# mainBoard_GTernal_1-0_v12.net
KiCad netlist of a schematic drawn in EAGLE
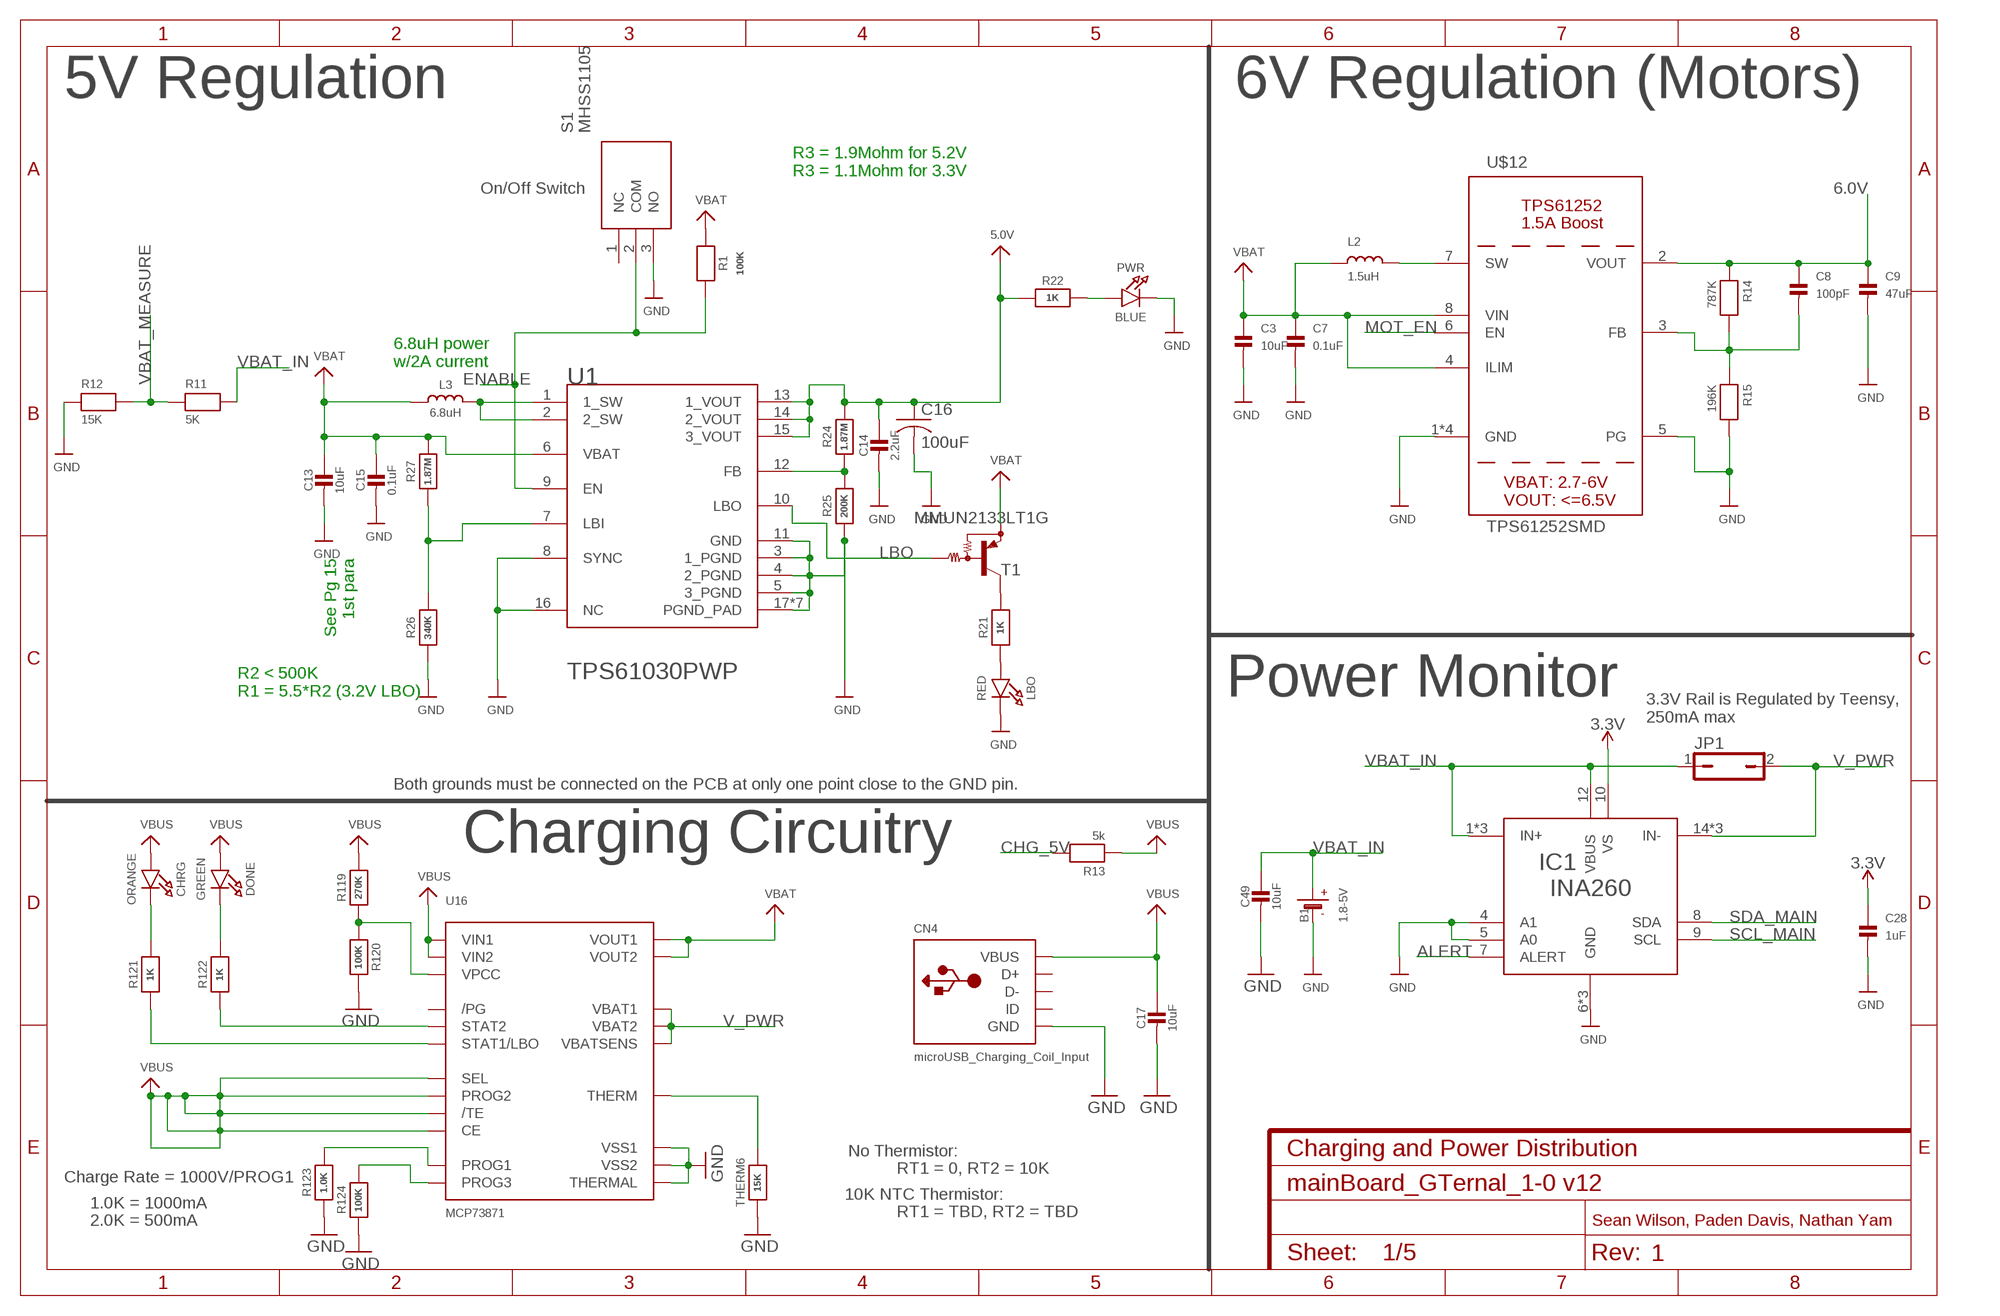
[diagram p0: schematic, sheet 1]
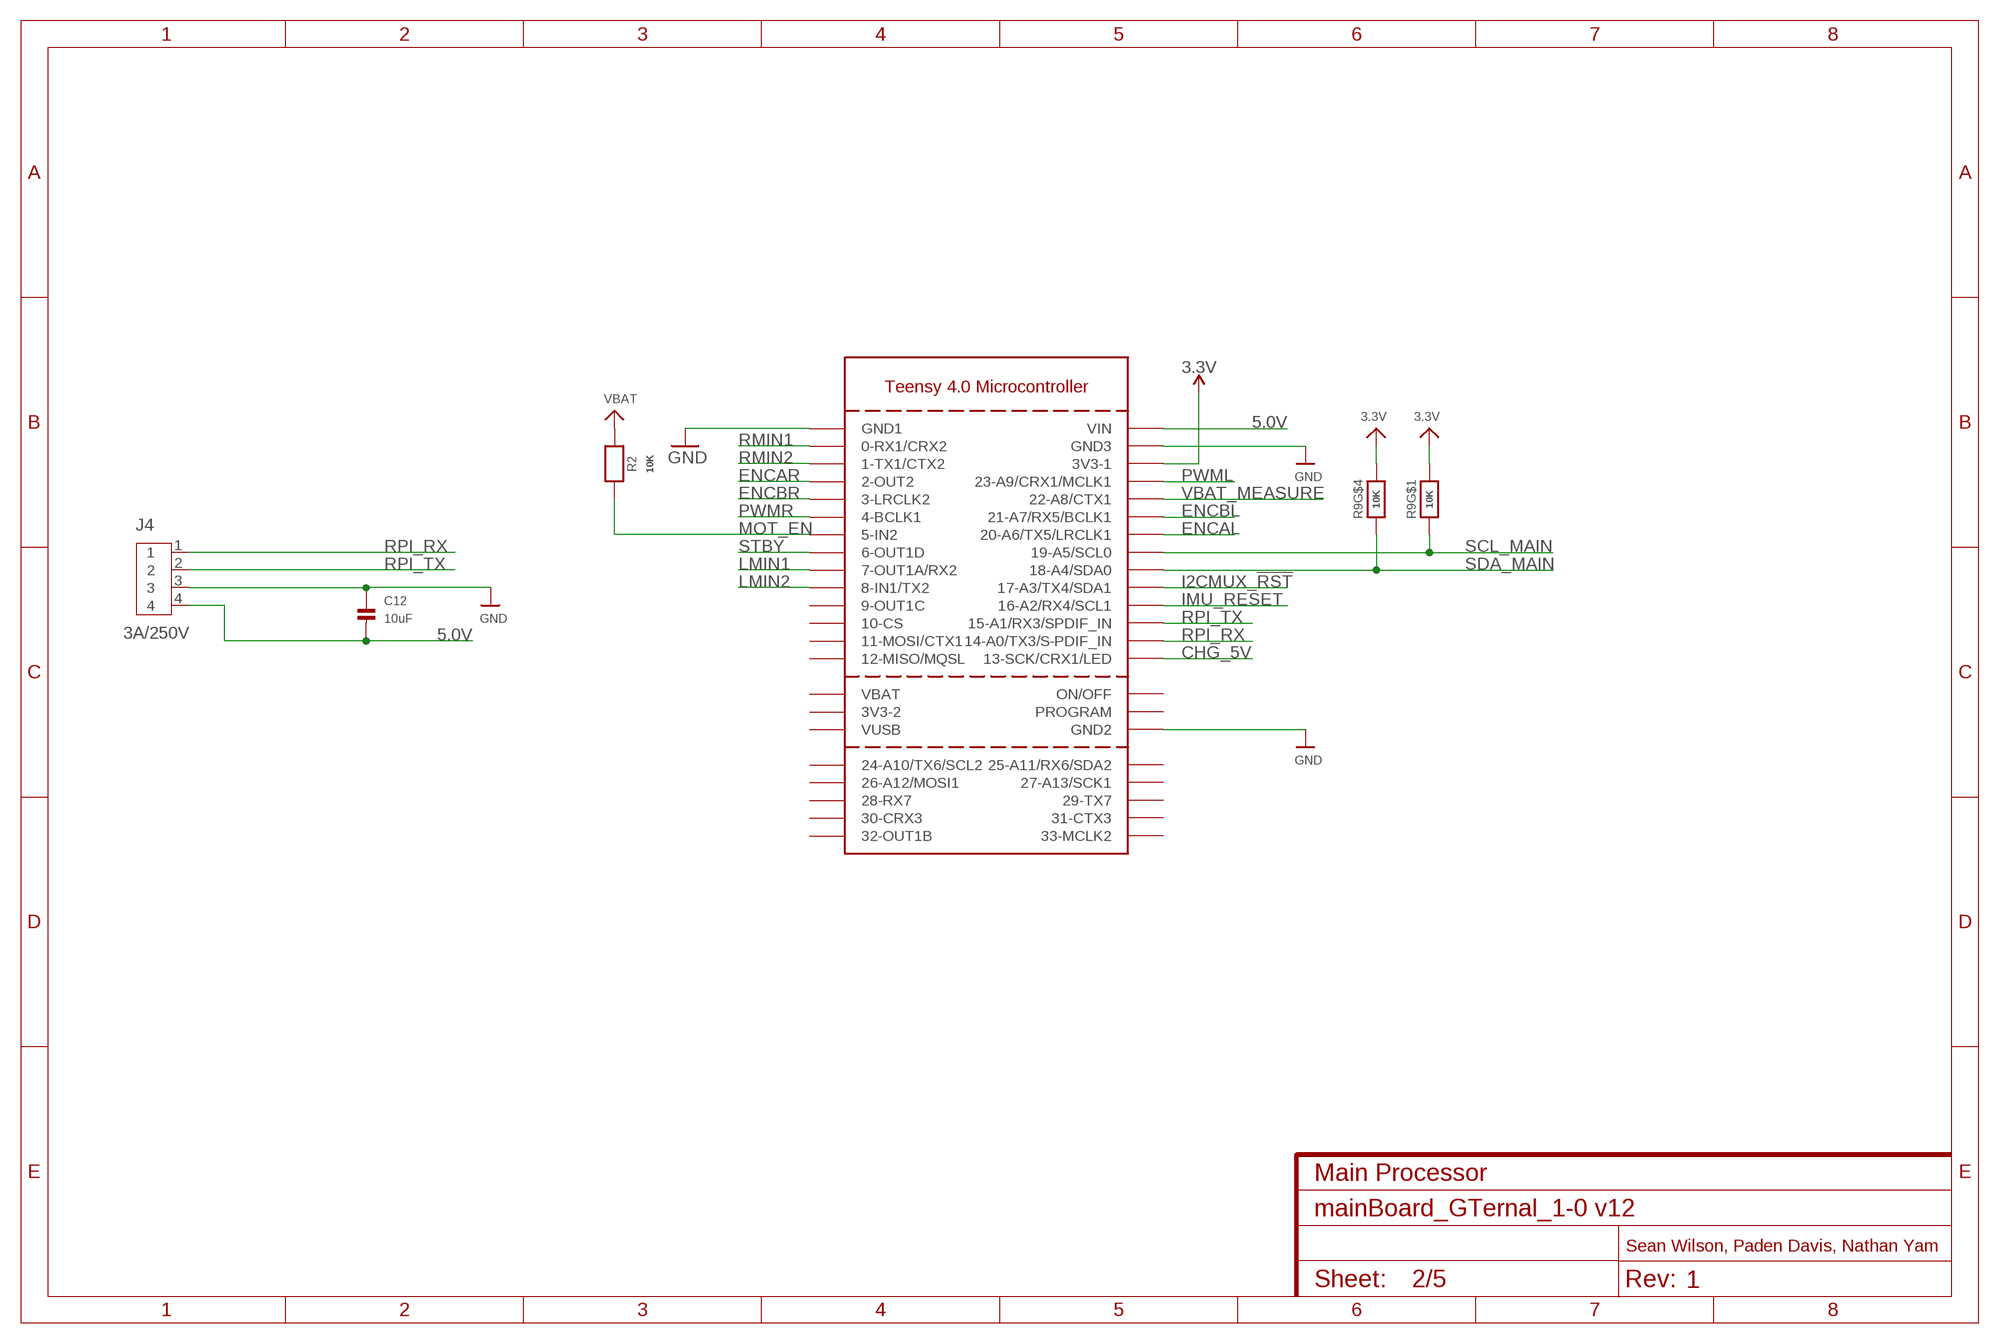
[diagram p1: schematic, sheet 2]
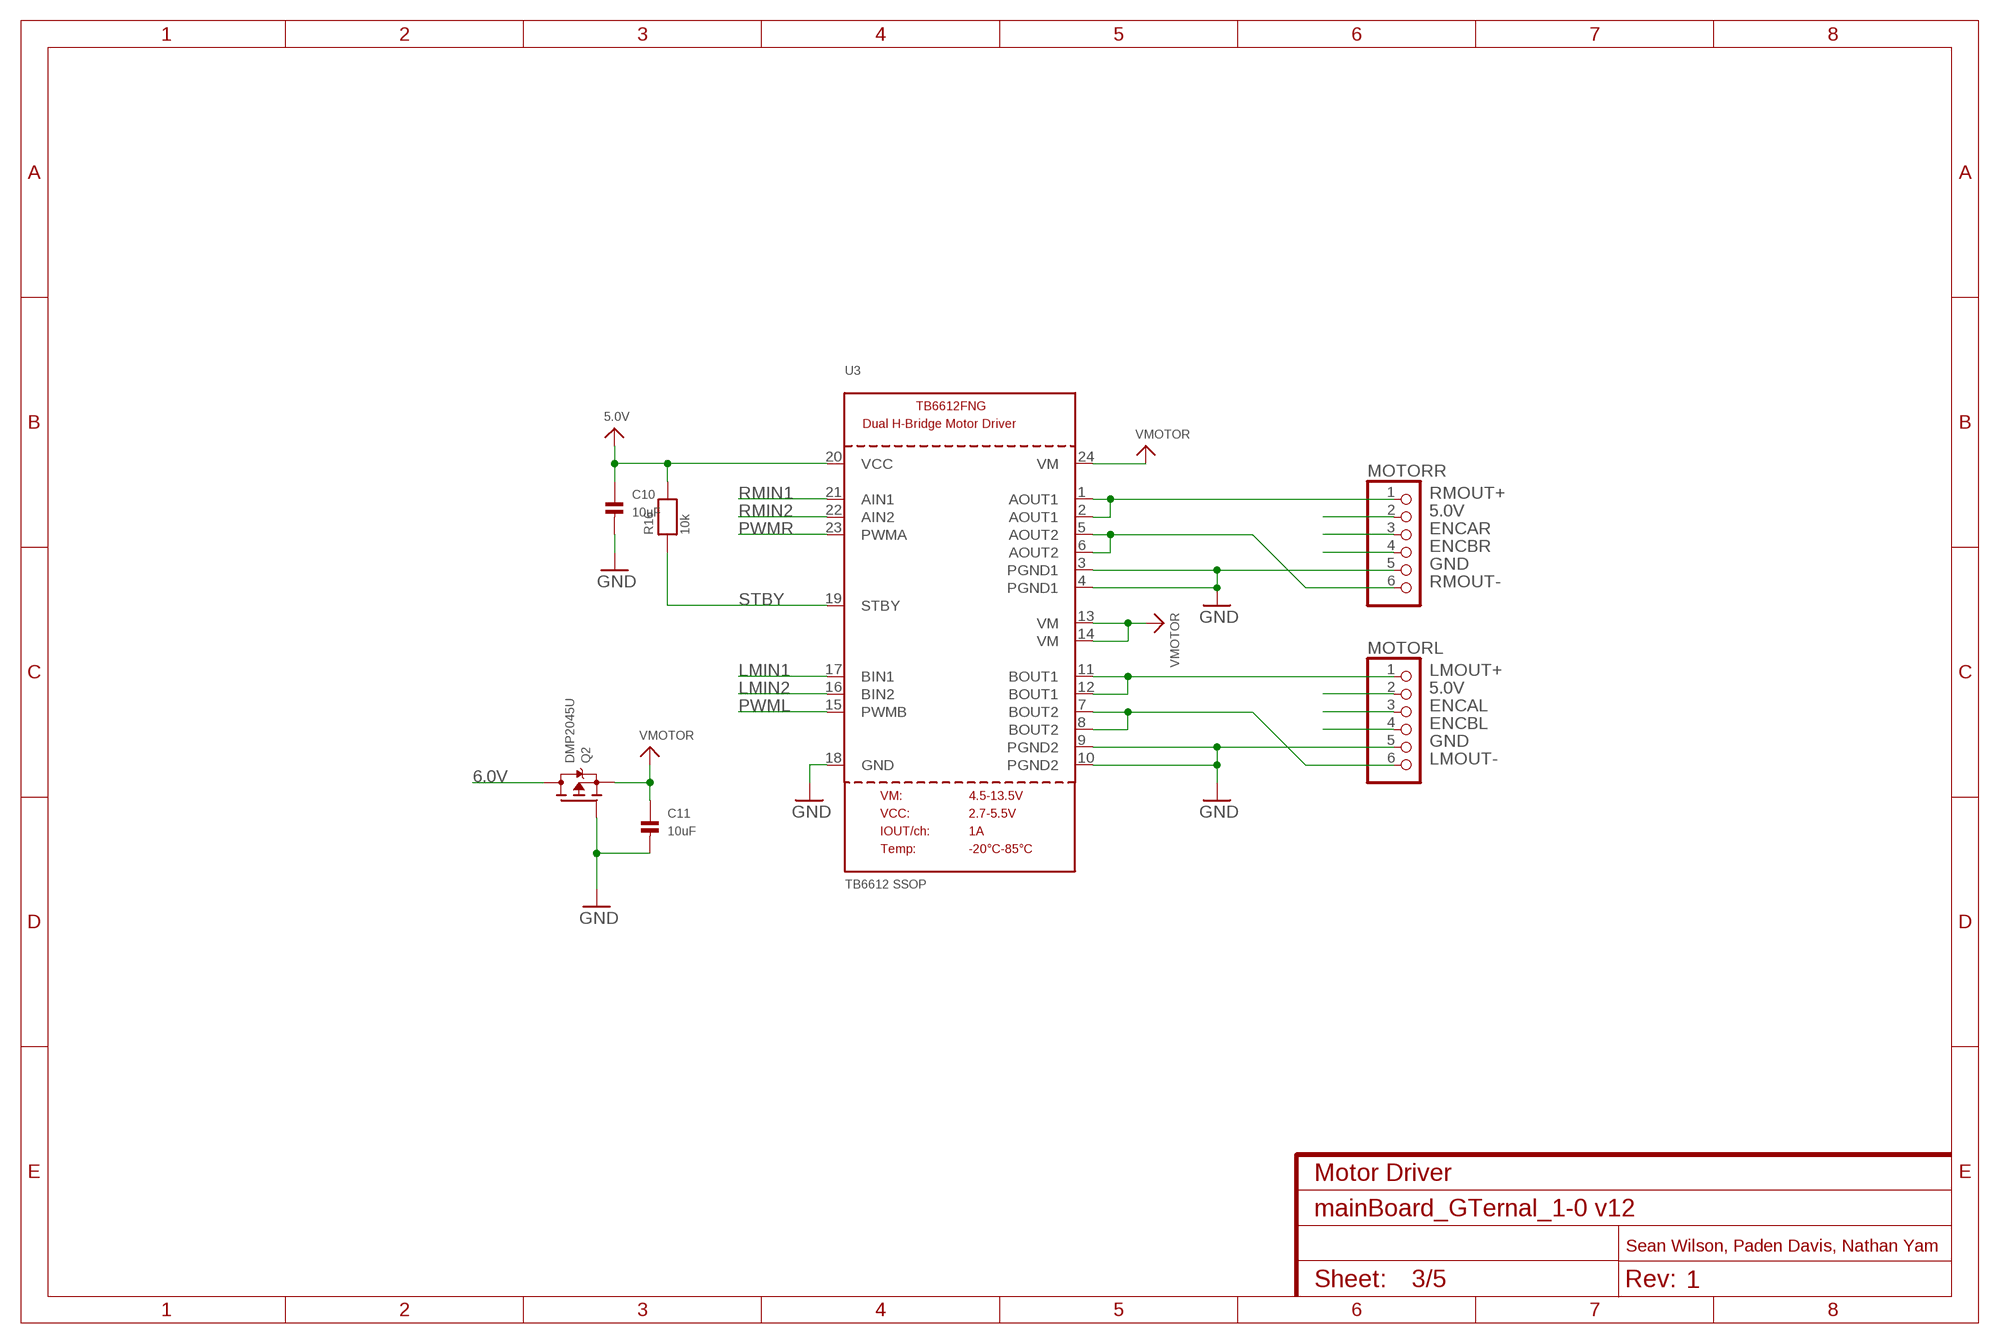
[diagram p2: schematic, sheet 3]
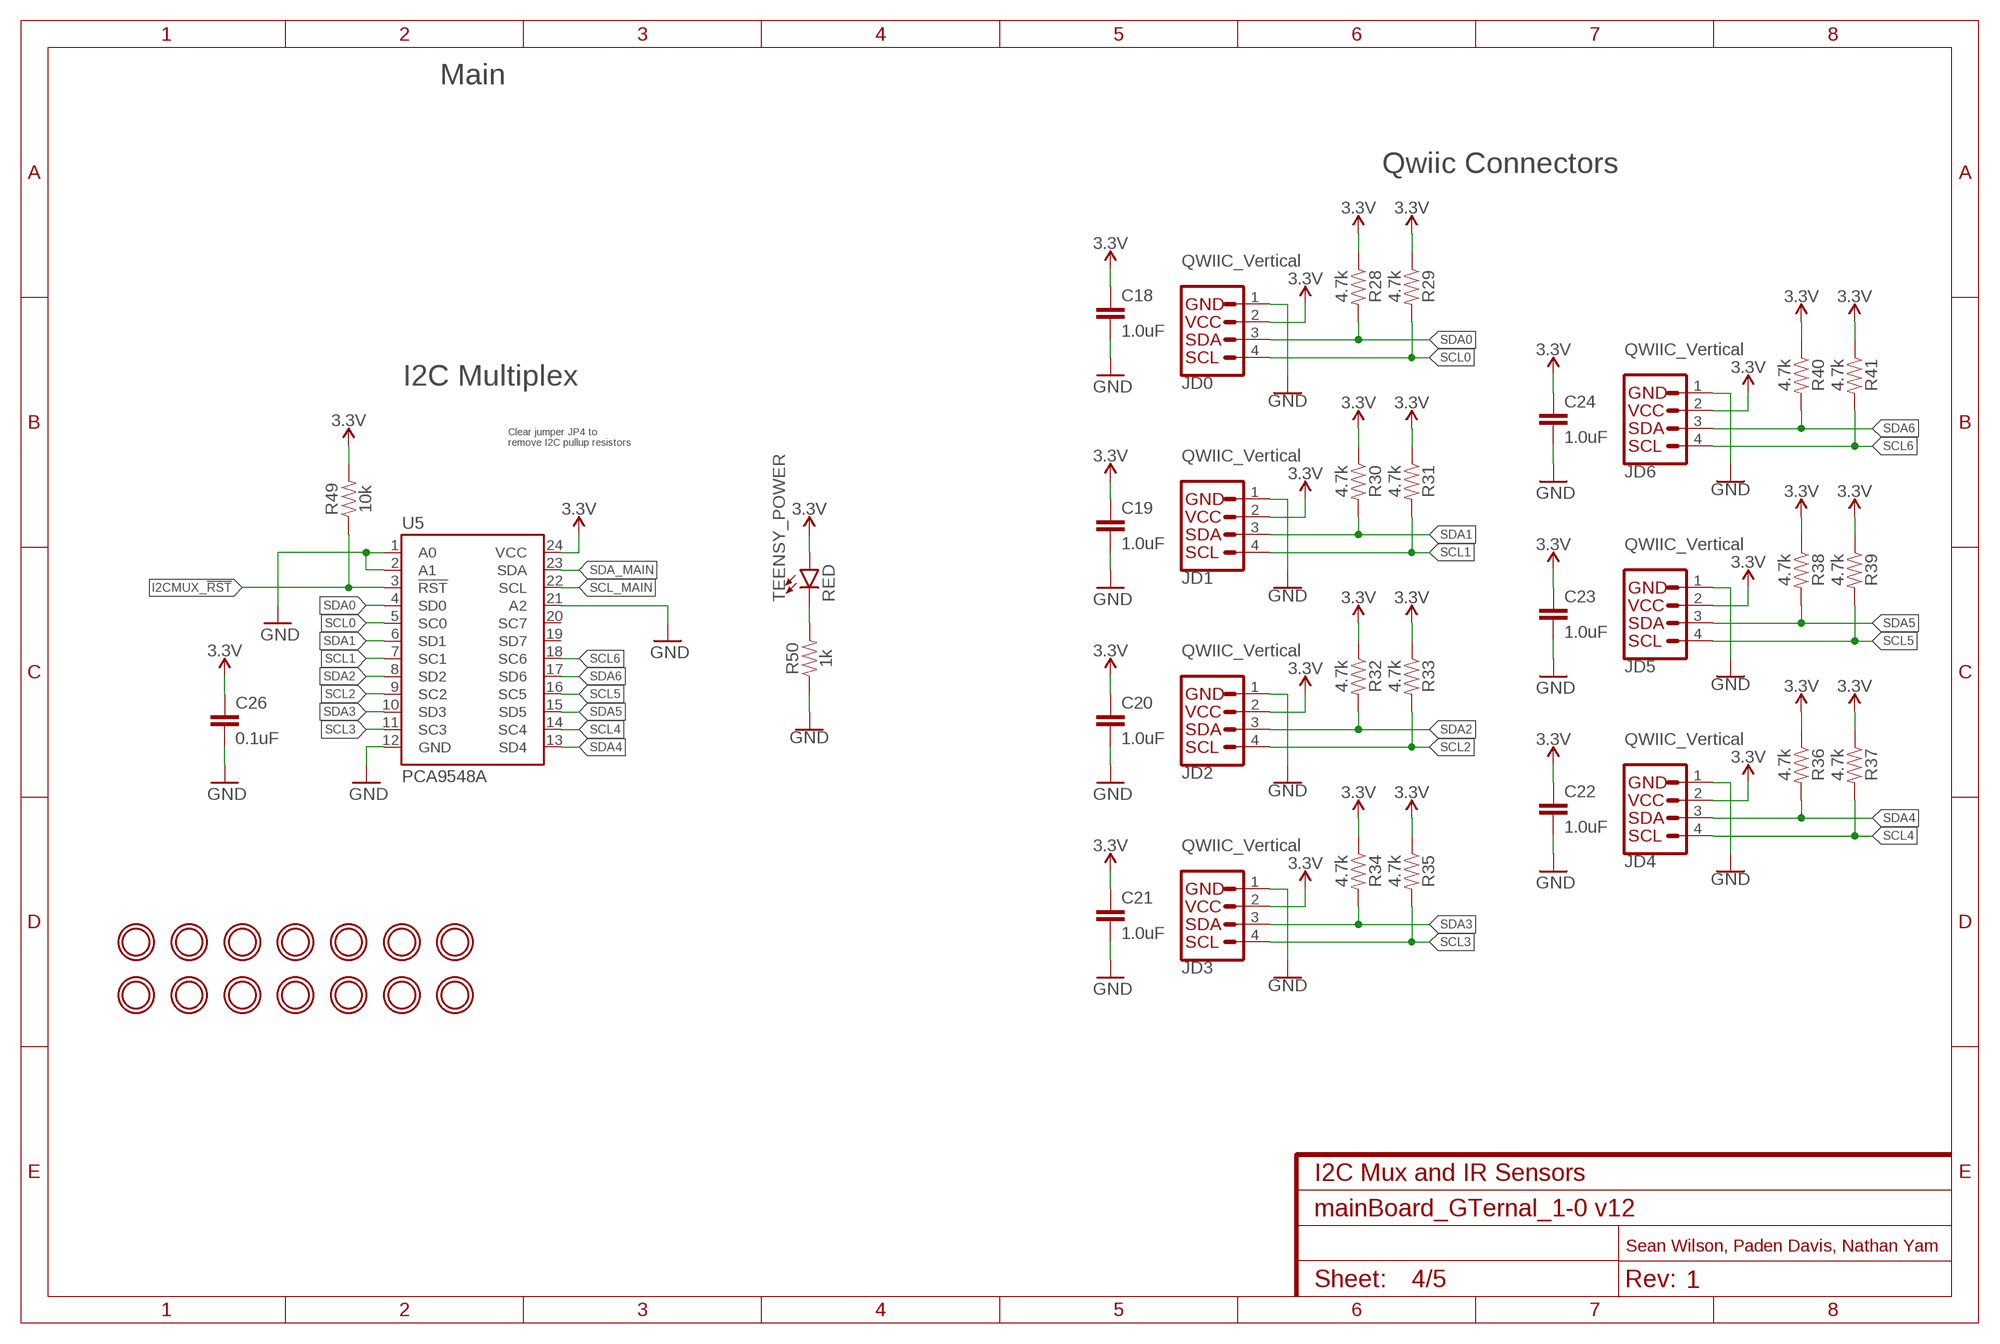
[diagram p3: schematic, sheet 4]
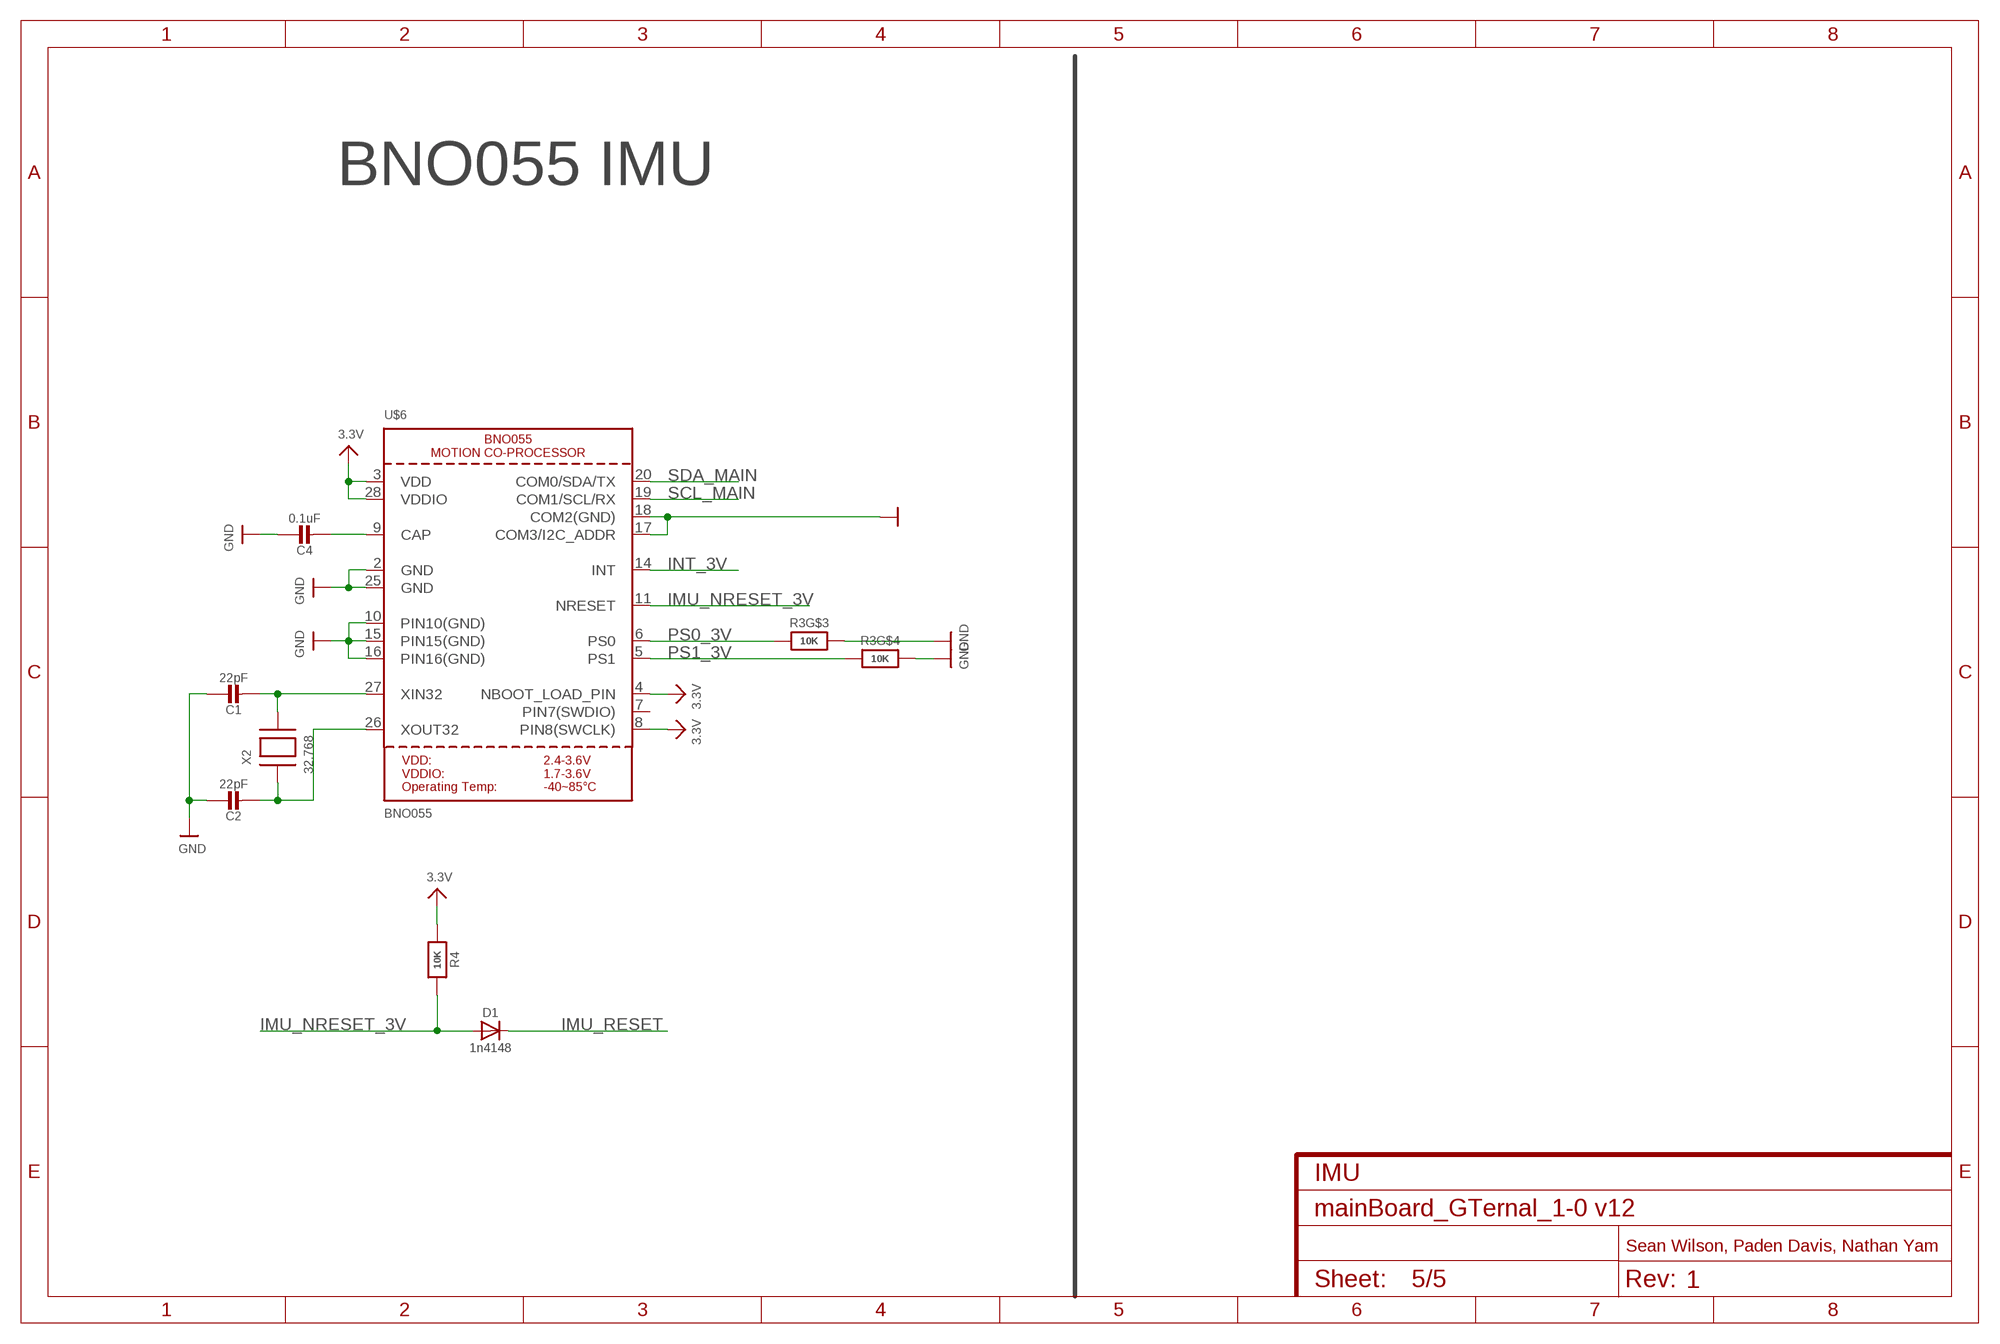
[diagram p4: schematic, sheet 5]

(export (version "E")
  (design (tool "Eeschema 10.0.6"))
  (components
    (comp (ref "C18")
      (value "1.0uF")
      (footprint "eagle-import:0603")
      (libsource (lib "eagle-import") (part "1.0UF-0603-16V-10%"))
    )
    (comp (ref "C19")
      (value "1.0uF")
      (footprint "eagle-import:0603")
      (libsource (lib "eagle-import") (part "1.0UF-0603-16V-10%"))
    )
    (comp (ref "C20")
      (value "1.0uF")
      (footprint "eagle-import:0603")
      (libsource (lib "eagle-import") (part "1.0UF-0603-16V-10%"))
    )
    (comp (ref "C21")
      (value "1.0uF")
      (footprint "eagle-import:0603")
      (libsource (lib "eagle-import") (part "1.0UF-0603-16V-10%"))
    )
    (comp (ref "C22")
      (value "1.0uF")
      (footprint "eagle-import:0603")
      (libsource (lib "eagle-import") (part "1.0UF-0603-16V-10%"))
    )
    (comp (ref "C23")
      (value "1.0uF")
      (footprint "eagle-import:0603")
      (libsource (lib "eagle-import") (part "1.0UF-0603-16V-10%"))
    )
    (comp (ref "C24")
      (value "1.0uF")
      (footprint "eagle-import:0603")
      (libsource (lib "eagle-import") (part "1.0UF-0603-16V-10%"))
    )
    (comp (ref "C26")
      (value "0.1uF")
      (footprint "eagle-import:0603")
      (libsource (lib "eagle-import") (part "0.1UF-0603-25V-(+80/-20%)"))
    )
    (comp (ref "JD0")
      (value "QWIIC_Vertical")
      (footprint "eagle-import:JST04_1MM_VERT")
      (libsource (lib "eagle-import") (part "QWIIC_CONNECTOR"))
    )
    (comp (ref "JD1")
      (value "QWIIC_Vertical")
      (footprint "eagle-import:JST04_1MM_VERT")
      (libsource (lib "eagle-import") (part "QWIIC_CONNECTOR"))
    )
    (comp (ref "JD2")
      (value "QWIIC_Vertical")
      (footprint "eagle-import:JST04_1MM_VERT")
      (libsource (lib "eagle-import") (part "QWIIC_CONNECTOR"))
    )
    (comp (ref "JD3")
      (value "QWIIC_Vertical")
      (footprint "eagle-import:JST04_1MM_VERT")
      (libsource (lib "eagle-import") (part "QWIIC_CONNECTOR"))
    )
    (comp (ref "JD4")
      (value "QWIIC_Vertical")
      (footprint "eagle-import:JST04_1MM_VERT")
      (libsource (lib "eagle-import") (part "QWIIC_CONNECTOR"))
    )
    (comp (ref "JD5")
      (value "QWIIC_Vertical")
      (footprint "eagle-import:JST04_1MM_VERT")
      (libsource (lib "eagle-import") (part "QWIIC_CONNECTOR"))
    )
    (comp (ref "JD6")
      (value "QWIIC_Vertical")
      (footprint "eagle-import:JST04_1MM_VERT")
      (libsource (lib "eagle-import") (part "QWIIC_CONNECTOR"))
    )
    (comp (ref "R28")
      (value "4.7k")
      (footprint "eagle-import:0603")
      (libsource (lib "eagle-import") (part "4.7KOHM-0603-1/10W-1%"))
    )
    (comp (ref "R29")
      (value "4.7k")
      (footprint "eagle-import:0603")
      (libsource (lib "eagle-import") (part "4.7KOHM-0603-1/10W-1%"))
    )
    (comp (ref "R30")
      (value "4.7k")
      (footprint "eagle-import:0603")
      (libsource (lib "eagle-import") (part "4.7KOHM-0603-1/10W-1%"))
    )
    (comp (ref "R31")
      (value "4.7k")
      (footprint "eagle-import:0603")
      (libsource (lib "eagle-import") (part "4.7KOHM-0603-1/10W-1%"))
    )
    (comp (ref "R32")
      (value "4.7k")
      (footprint "eagle-import:0603")
      (libsource (lib "eagle-import") (part "4.7KOHM-0603-1/10W-1%"))
    )
    (comp (ref "R33")
      (value "4.7k")
      (footprint "eagle-import:0603")
      (libsource (lib "eagle-import") (part "4.7KOHM-0603-1/10W-1%"))
    )
    (comp (ref "R34")
      (value "4.7k")
      (footprint "eagle-import:0603")
      (libsource (lib "eagle-import") (part "4.7KOHM-0603-1/10W-1%"))
    )
    (comp (ref "R35")
      (value "4.7k")
      (footprint "eagle-import:0603")
      (libsource (lib "eagle-import") (part "4.7KOHM-0603-1/10W-1%"))
    )
    (comp (ref "R36")
      (value "4.7k")
      (footprint "eagle-import:0603")
      (libsource (lib "eagle-import") (part "4.7KOHM-0603-1/10W-1%"))
    )
    (comp (ref "R37")
      (value "4.7k")
      (footprint "eagle-import:0603")
      (libsource (lib "eagle-import") (part "4.7KOHM-0603-1/10W-1%"))
    )
    (comp (ref "R38")
      (value "4.7k")
      (footprint "eagle-import:0603")
      (libsource (lib "eagle-import") (part "4.7KOHM-0603-1/10W-1%"))
    )
    (comp (ref "R39")
      (value "4.7k")
      (footprint "eagle-import:0603")
      (libsource (lib "eagle-import") (part "4.7KOHM-0603-1/10W-1%"))
    )
    (comp (ref "R40")
      (value "4.7k")
      (footprint "eagle-import:0603")
      (libsource (lib "eagle-import") (part "4.7KOHM-0603-1/10W-1%"))
    )
    (comp (ref "R41")
      (value "4.7k")
      (footprint "eagle-import:0603")
      (libsource (lib "eagle-import") (part "4.7KOHM-0603-1/10W-1%"))
    )
    (comp (ref "R49")
      (value "10k")
      (footprint "eagle-import:0603")
      (libsource (lib "eagle-import") (part "10KOHM-0603-1/10W-1%"))
    )
    (comp (ref "R50")
      (value "1k")
      (footprint "eagle-import:0603")
      (libsource (lib "eagle-import") (part "1KOHM-0603-1/10W-1%"))
    )
    (comp (ref "TEENSY_POWER")
      (value "RED")
      (footprint "eagle-import:LED-0603")
      (libsource (lib "eagle-import") (part "LED-RED0603"))
    )
    (comp (ref "U$8")
      (value "MOUNTINGHOLE2.5")
      (footprint "eagle-import:MOUNTINGHOLE_2.5_PLATED")
      (libsource (lib "eagle-import") (part "MOUNTINGHOLE2.5"))
    )
    (comp (ref "U$30")
      (value "MOUNTINGHOLE2.5")
      (footprint "eagle-import:MOUNTINGHOLE_2.5_PLATED")
      (libsource (lib "eagle-import") (part "MOUNTINGHOLE2.5"))
    )
    (comp (ref "U$31")
      (value "MOUNTINGHOLE2.5")
      (footprint "eagle-import:MOUNTINGHOLE_2.5_PLATED")
      (libsource (lib "eagle-import") (part "MOUNTINGHOLE2.5"))
    )
    (comp (ref "U$32")
      (value "MOUNTINGHOLE2.5")
      (footprint "eagle-import:MOUNTINGHOLE_2.5_PLATED")
      (libsource (lib "eagle-import") (part "MOUNTINGHOLE2.5"))
    )
    (comp (ref "U$33")
      (value "MOUNTINGHOLE2.5")
      (footprint "eagle-import:MOUNTINGHOLE_2.5_PLATED")
      (libsource (lib "eagle-import") (part "MOUNTINGHOLE2.5"))
    )
    (comp (ref "U$34")
      (value "MOUNTINGHOLE2.5")
      (footprint "eagle-import:MOUNTINGHOLE_2.5_PLATED")
      (libsource (lib "eagle-import") (part "MOUNTINGHOLE2.5"))
    )
    (comp (ref "U$35")
      (value "MOUNTINGHOLE2.5")
      (footprint "eagle-import:MOUNTINGHOLE_2.5_PLATED")
      (libsource (lib "eagle-import") (part "MOUNTINGHOLE2.5"))
    )
    (comp (ref "U$36")
      (value "MOUNTINGHOLE2.5")
      (footprint "eagle-import:MOUNTINGHOLE_2.5_PLATED")
      (libsource (lib "eagle-import") (part "MOUNTINGHOLE2.5"))
    )
    (comp (ref "U$37")
      (value "MOUNTINGHOLE2.5")
      (footprint "eagle-import:MOUNTINGHOLE_2.5_PLATED")
      (libsource (lib "eagle-import") (part "MOUNTINGHOLE2.5"))
    )
    (comp (ref "U$43")
      (value "MOUNTINGHOLE2.5")
      (footprint "eagle-import:MOUNTINGHOLE_2.5_PLATED")
      (libsource (lib "eagle-import") (part "MOUNTINGHOLE2.5"))
    )
    (comp (ref "U$45")
      (value "MOUNTINGHOLE2.5")
      (footprint "eagle-import:MOUNTINGHOLE_2.5_PLATED")
      (libsource (lib "eagle-import") (part "MOUNTINGHOLE2.5"))
    )
    (comp (ref "U$46")
      (value "MOUNTINGHOLE2.5")
      (footprint "eagle-import:MOUNTINGHOLE_2.5_PLATED")
      (libsource (lib "eagle-import") (part "MOUNTINGHOLE2.5"))
    )
    (comp (ref "U$47")
      (value "MOUNTINGHOLE2.5")
      (footprint "eagle-import:MOUNTINGHOLE_2.5_PLATED")
      (libsource (lib "eagle-import") (part "MOUNTINGHOLE2.5"))
    )
    (comp (ref "U$48")
      (value "MOUNTINGHOLE2.5")
      (footprint "eagle-import:MOUNTINGHOLE_2.5_PLATED")
      (libsource (lib "eagle-import") (part "MOUNTINGHOLE2.5"))
    )
    (comp (ref "U5")
      (value "PCA9548A")
      (footprint "eagle-import:TSSOP28")
      (libsource (lib "eagle-import") (part "PCA9548A"))
    )
    (comp (ref "C1")
      (value "22pF")
      (footprint "eagle-import:0603-NO")
      (libsource (lib "eagle-import") (part "CAP_CERAMIC0603_NO"))
    )
    (comp (ref "C2")
      (value "22pF")
      (footprint "eagle-import:0603-NO")
      (libsource (lib "eagle-import") (part "CAP_CERAMIC0603_NO"))
    )
    (comp (ref "C4")
      (value "0.1uF")
      (footprint "eagle-import:0603-NO")
      (libsource (lib "eagle-import") (part "CAP_CERAMIC0603_NO"))
    )
    (comp (ref "D1")
      (value "1n4148")
      (footprint "eagle-import:SOD-323")
      (libsource (lib "eagle-import") (part "DIODESOD-323"))
    )
    (comp (ref "R3")
      (value "10K")
      (footprint "eagle-import:RESPACK_4X0603")
      (libsource (lib "eagle-import") (part "RESISTOR_4PACK"))
    )
    (comp (ref "R4")
      (value "10K")
      (footprint "eagle-import:0603-NO")
      (libsource (lib "eagle-import") (part "RESISTOR_0603_NOOUT"))
    )
    (comp (ref "U$6")
      (value "BNO055")
      (footprint "eagle-import:BNO055")
      (libsource (lib "eagle-import") (part "BNO055"))
    )
    (comp (ref "X2")
      (value "32.768")
      (footprint "eagle-import:XTAL3215")
      (libsource (lib "eagle-import") (part "XTAL-3.2X1.5"))
    )
    (comp (ref "C10")
      (value "10uF")
      (footprint "eagle-import:0603")
      (libsource (lib "eagle-import") (part "CAP_CERAMIC0603"))
    )
    (comp (ref "C11")
      (value "10uF")
      (footprint "eagle-import:0603")
      (libsource (lib "eagle-import") (part "CAP_CERAMIC0603"))
    )
    (comp (ref "MOTORL")
      (value "PINHD-1X6CB")
      (footprint "eagle-import:1X06-CLEANBIG")
      (libsource (lib "eagle-import") (part "PINHD-1X6CB"))
    )
    (comp (ref "MOTORR")
      (value "PINHD-1X6CB")
      (footprint "eagle-import:1X06-CLEANBIG")
      (libsource (lib "eagle-import") (part "PINHD-1X6CB"))
    )
    (comp (ref "Q2")
      (value "DMP2045U")
      (footprint "eagle-import:SOT23-WIDE")
      (libsource (lib "eagle-import") (part "MOSFET-PWIDE"))
    )
    (comp (ref "R16")
      (value "10k")
      (footprint "eagle-import:0805")
      (libsource (lib "eagle-import") (part "RESISTOR0805"))
    )
    (comp (ref "U3")
      (value "TB6612 SSOP")
      (footprint "eagle-import:SSOP24")
      (libsource (lib "eagle-import") (part "TB6612FNGSSOP"))
    )
    (comp (ref "C12")
      (value "10uF")
      (footprint "eagle-import:0603")
      (libsource (lib "eagle-import") (part "CAP_CERAMIC0603"))
    )
    (comp (ref "J4")
      (value "3A/250V")
      (footprint "eagle-import:B4B-XH-A")
      (fields (field (name "MANUFACTURER") "JST (XH connector)") (field (name "MPN") "B4B-XH-A"))
      (libsource (lib "eagle-import") (part "B4B-XH-A"))
    )
    (comp (ref "R2")
      (value "10K")
      (footprint "eagle-import:0805-NO")
      (libsource (lib "eagle-import") (part "RESISTOR0805_NOOUTLINE"))
    )
    (comp (ref "R9")
      (value "10K")
      (footprint "eagle-import:RESPACK_4X0603")
      (libsource (lib "eagle-import") (part "RESISTOR_4PACK"))
    )
    (comp (ref "U$57")
      (value "TEENSY40")
      (footprint "eagle-import:TEENSY40")
      (libsource (lib "eagle-import") (part "TEENSY40"))
    )
    (comp (ref "B1")
      (value "1.8-5V")
      (footprint "eagle-import:JSTPH2")
      (libsource (lib "eagle-import") (part "BATTERY"))
    )
    (comp (ref "C3")
      (value "10uF")
      (footprint "eagle-import:0603")
      (libsource (lib "eagle-import") (part "CAP_CERAMIC0603"))
    )
    (comp (ref "C7")
      (value "0.1uF")
      (footprint "eagle-import:0805")
      (libsource (lib "eagle-import") (part "CAP_CERAMIC0805"))
    )
    (comp (ref "C8")
      (value "100pF")
      (footprint "eagle-import:0603")
      (libsource (lib "eagle-import") (part "CAP_CERAMIC0603"))
    )
    (comp (ref "C9")
      (value "47uF")
      (footprint "eagle-import:1206")
      (libsource (lib "eagle-import") (part "CAP_CERAMIC1206"))
    )
    (comp (ref "C13")
      (value "10uF")
      (footprint "eagle-import:0805-NO")
      (libsource (lib "eagle-import") (part "CAP_CERAMIC0805-NOOUTLINE"))
    )
    (comp (ref "C14")
      (value "2.2uF")
      (footprint "eagle-import:0805-NO")
      (libsource (lib "eagle-import") (part "CAP_CERAMIC0805-NOOUTLINE"))
    )
    (comp (ref "C15")
      (value "0.1uF")
      (footprint "eagle-import:0805_10MGAP")
      (libsource (lib "eagle-import") (part "CAP_CERAMIC0805_10MGAP"))
    )
    (comp (ref "C16")
      (value "100uF")
      (footprint "eagle-import:C1210")
      (libsource (lib "eagle-import") (part "C-USC1210"))
    )
    (comp (ref "C17")
      (value "10uF")
      (footprint "eagle-import:0805-NO")
      (libsource (lib "eagle-import") (part "CAP_CERAMIC0805-NOOUTLINE"))
    )
    (comp (ref "C28")
      (value "1uF")
      (footprint "eagle-import:0603-NO")
      (libsource (lib "eagle-import") (part "CAP_CERAMIC0603_NO"))
    )
    (comp (ref "C49")
      (value "10uF")
      (footprint "eagle-import:0805-NO")
      (libsource (lib "eagle-import") (part "CAP_CERAMIC0805-NOOUTLINE"))
    )
    (comp (ref "CHRG")
      (value "ORANGE")
      (footprint "eagle-import:CHIPLED_0805_NOOUTLINE")
      (libsource (lib "eagle-import") (part "LED0805_NOOUTLINE"))
    )
    (comp (ref "CN4")
      (value "microUSB_Charging_Coil_Input")
      (footprint "eagle-import:4UCONN_20329")
      (libsource (lib "eagle-import") (part "USBMICRO_20329"))
    )
    (comp (ref "DONE")
      (value "GREEN")
      (footprint "eagle-import:CHIPLED_0805_NOOUTLINE")
      (libsource (lib "eagle-import") (part "LED0805_NOOUTLINE"))
    )
    (comp (ref "IC1")
      (value "INA260")
      (footprint "eagle-import:TSSOP16")
      (libsource (lib "eagle-import") (part "INA260"))
    )
    (comp (ref "JP1")
      (value "JP1Q")
      (footprint "eagle-import:JP1")
      (libsource (lib "eagle-import") (part "JP1Q"))
    )
    (comp (ref "L2")
      (value "1.5uH")
      (footprint "eagle-import:MURATA_DFE252012P-1R5M=P2")
      (libsource (lib "eagle-import") (part "MURATA_DFE252012P-1R5M=P2"))
    )
    (comp (ref "L3")
      (value "6.8uH")
      (footprint "eagle-import:INDUCTOR_5X5MM_TDK_VLC5045")
      (libsource (lib "eagle-import") (part "INDUCTORTDK_VLC5045"))
    )
    (comp (ref "LBO")
      (value "RED")
      (footprint "eagle-import:CHIPLED_0805_NOOUTLINE")
      (libsource (lib "eagle-import") (part "LED0805_NOOUTLINE"))
    )
    (comp (ref "PWR")
      (value "BLUE")
      (footprint "eagle-import:CHIPLED_0805_NOOUTLINE")
      (libsource (lib "eagle-import") (part "LED0805_NOOUTLINE"))
    )
    (comp (ref "R1")
      (value "100K")
      (footprint "eagle-import:0805-NO")
      (libsource (lib "eagle-import") (part "RESISTOR0805_NOOUTLINE"))
    )
    (comp (ref "R11")
      (value "5K")
      (footprint "eagle-import:0805")
      (libsource (lib "eagle-import") (part "RESISTOR0805"))
    )
    (comp (ref "R12")
      (value "15K")
      (footprint "eagle-import:0805")
      (libsource (lib "eagle-import") (part "RESISTOR0805"))
    )
    (comp (ref "R13")
      (value "5k")
      (footprint "eagle-import:0805")
      (libsource (lib "eagle-import") (part "RESISTOR0805"))
    )
    (comp (ref "R14")
      (value "787K")
      (footprint "eagle-import:0805")
      (libsource (lib "eagle-import") (part "RESISTOR0805"))
    )
    (comp (ref "R15")
      (value "196K")
      (footprint "eagle-import:0805")
      (libsource (lib "eagle-import") (part "RESISTOR0805"))
    )
    (comp (ref "R21")
      (value "1K")
      (footprint "eagle-import:0805-NO")
      (libsource (lib "eagle-import") (part "RESISTOR0805_NOOUTLINE"))
    )
    (comp (ref "R22")
      (value "1K")
      (footprint "eagle-import:0805-NO")
      (libsource (lib "eagle-import") (part "RESISTOR0805_NOOUTLINE"))
    )
    (comp (ref "R24")
      (value "1.87M")
      (footprint "eagle-import:0805-NO")
      (libsource (lib "eagle-import") (part "RESISTOR0805_NOOUTLINE"))
    )
    (comp (ref "R25")
      (value "200K")
      (footprint "eagle-import:0805-NO")
      (libsource (lib "eagle-import") (part "RESISTOR0805_NOOUTLINE"))
    )
    (comp (ref "R26")
      (value "340K")
      (footprint "eagle-import:_0805MP")
      (libsource (lib "eagle-import") (part "microbuilder_vf.jQhFfLl6SwyupizEU6PNDA_RESISTOR_0805MP"))
    )
    (comp (ref "R27")
      (value "1.87M")
      (footprint "eagle-import:_0805MP")
      (libsource (lib "eagle-import") (part "microbuilder_vf.jQhFfLl6SwyupizEU6PNDA_RESISTOR_0805MP"))
    )
    (comp (ref "R119")
      (value "270K")
      (footprint "eagle-import:0805-NO")
      (libsource (lib "eagle-import") (part "RESISTOR0805_NOOUTLINE"))
    )
    (comp (ref "R120")
      (value "100K")
      (footprint "eagle-import:0805-NO")
      (libsource (lib "eagle-import") (part "RESISTOR0805_NOOUTLINE"))
    )
    (comp (ref "R121")
      (value "1K")
      (footprint "eagle-import:0805-NO")
      (libsource (lib "eagle-import") (part "RESISTOR0805_NOOUTLINE"))
    )
    (comp (ref "R122")
      (value "1K")
      (footprint "eagle-import:0805-NO")
      (libsource (lib "eagle-import") (part "RESISTOR0805_NOOUTLINE"))
    )
    (comp (ref "R123")
      (value "1.0K")
      (footprint "eagle-import:0805-NO")
      (libsource (lib "eagle-import") (part "RESISTOR0805_NOOUTLINE"))
    )
    (comp (ref "R124")
      (value "100K")
      (footprint "eagle-import:0805-NO")
      (libsource (lib "eagle-import") (part "RESISTOR0805_NOOUTLINE"))
    )
    (comp (ref "S1")
      (value "MHSS1105")
      (footprint "eagle-import:MHSS1105")
      (fields (field (name "MOUSER_PART_NUMBER") "642-MHSS1105"))
      (libsource (lib "eagle-import") (part "MHSS1105"))
    )
    (comp (ref "T1")
      (value "MMUN2133LT1G")
      (footprint "eagle-import:SC59-BEC")
      (libsource (lib "eagle-import") (part "-PNP_DRIVER-SC59-BECMUN2114T1"))
    )
    (comp (ref "THERM6")
      (value "15K")
      (footprint "eagle-import:0805-NO")
      (libsource (lib "eagle-import") (part "RESISTOR0805_NOOUTLINE"))
    )
    (comp (ref "U$12")
      (value "TPS61252SMD")
      (footprint "eagle-import:TPS61252")
      (libsource (lib "eagle-import") (part "TPS61252SMD"))
    )
    (comp (ref "U1")
      (value "TEXAS_INSTRUMENTS_TPS61030PWPTEXAS_INSTRUMENTS_TPS61030PWP_0_0")
      (footprint "eagle-import:TEXAS_INSTRUMENTS_TPS61030PWP_0")
      (fields
        (field (name "DIGIKEY_PART_NUMBER") "296-27006-5-ND")
        (field (name "MF") "Texas Instruments")
        (field (name "MOUSER_PART_NUMBER") "595-TPS61030PWP")
      )
      (libsource (lib "eagle-import") (part "TEXAS_INSTRUMENTS_TPS61030PWPTEXAS_INSTRUMENTS_TPS61030PWP_0_0"))
    )
    (comp (ref "U16")
      (value "MCP73871")
      (footprint "eagle-import:QFN20_4MM")
      (libsource (lib "eagle-import") (part "MCP73871"))
    )
  )
  (nets
    (net (code "1") (name "3.3V") (class "Default")
      (node (ref "C18") (pin "1") (pinfunction "1_1") (pintype "passive"))
      (node (ref "C19") (pin "1") (pinfunction "1_1") (pintype "passive"))
      (node (ref "C20") (pin "1") (pinfunction "1_1") (pintype "passive"))
      (node (ref "C21") (pin "1") (pinfunction "1_1") (pintype "passive"))
      (node (ref "C22") (pin "1") (pinfunction "1_1") (pintype "passive"))
      (node (ref "C23") (pin "1") (pinfunction "1_1") (pintype "passive"))
      (node (ref "C24") (pin "1") (pinfunction "1_1") (pintype "passive"))
      (node (ref "C26") (pin "1") (pinfunction "1_1") (pintype "passive"))
      (node (ref "C28") (pin "1") (pinfunction "1_1") (pintype "passive"))
      (node (ref "IC1") (pin "10") (pinfunction "VS_10") (pintype "power_in"))
      (node (ref "JD0") (pin "2") (pinfunction "2_2") (pintype "power_in"))
      (node (ref "JD1") (pin "2") (pinfunction "2_2") (pintype "power_in"))
      (node (ref "JD2") (pin "2") (pinfunction "2_2") (pintype "power_in"))
      (node (ref "JD3") (pin "2") (pinfunction "2_2") (pintype "power_in"))
      (node (ref "JD4") (pin "2") (pinfunction "2_2") (pintype "power_in"))
      (node (ref "JD5") (pin "2") (pinfunction "2_2") (pintype "power_in"))
      (node (ref "JD6") (pin "2") (pinfunction "2_2") (pintype "power_in"))
      (node (ref "R28") (pin "1") (pinfunction "1_1") (pintype "passive"))
      (node (ref "R29") (pin "1") (pinfunction "1_1") (pintype "passive"))
      (node (ref "R30") (pin "1") (pinfunction "1_1") (pintype "passive"))
      (node (ref "R31") (pin "1") (pinfunction "1_1") (pintype "passive"))
      (node (ref "R32") (pin "1") (pinfunction "1_1") (pintype "passive"))
      (node (ref "R33") (pin "1") (pinfunction "1_1") (pintype "passive"))
      (node (ref "R34") (pin "1") (pinfunction "1_1") (pintype "passive"))
      (node (ref "R35") (pin "1") (pinfunction "1_1") (pintype "passive"))
      (node (ref "R36") (pin "1") (pinfunction "1_1") (pintype "passive"))
      (node (ref "R37") (pin "1") (pinfunction "1_1") (pintype "passive"))
      (node (ref "R38") (pin "1") (pinfunction "1_1") (pintype "passive"))
      (node (ref "R39") (pin "1") (pinfunction "1_1") (pintype "passive"))
      (node (ref "R4") (pin "1") (pinfunction "1_1") (pintype "passive"))
      (node (ref "R40") (pin "1") (pinfunction "1_1") (pintype "passive"))
      (node (ref "R41") (pin "1") (pinfunction "1_1") (pintype "passive"))
      (node (ref "R49") (pin "2") (pinfunction "2_2") (pintype "passive"))
      (node (ref "R9") (pin "1") (pinfunction "1_1") (pintype "passive"))
      (node (ref "R9") (pin "4") (pinfunction "1_4") (pintype "passive"))
      (node (ref "TEENSY_POWER") (pin "A") (pinfunction "A_A") (pintype "passive"))
      (node (ref "U$57") (pin "3V3-1") (pinfunction "3V3-1_3V3-1") (pintype "bidirectional"))
      (node (ref "U$6") (pin "28") (pinfunction "VDDIO_28") (pintype "power_in"))
      (node (ref "U$6") (pin "3") (pinfunction "VDD_3") (pintype "power_in"))
      (node (ref "U$6") (pin "4") (pinfunction "NBOOT_LOAD_PIN_4") (pintype "bidirectional"))
      (node (ref "U$6") (pin "8") (pinfunction "PIN8(SWCLK)_8") (pintype "bidirectional"))
      (node (ref "U5") (pin "24") (pinfunction "VCC_24") (pintype "bidirectional"))
    )
    (net (code "2") (name "5.0V") (class "Default")
      (node (ref "C10") (pin "1") (pinfunction "P$1_1") (pintype "passive"))
      (node (ref "C12") (pin "2") (pinfunction "P$2_2") (pintype "passive"))
      (node (ref "C14") (pin "1") (pinfunction "1_1") (pintype "passive"))
      (node (ref "C16") (pin "1") (pinfunction "1_1") (pintype "passive"))
      (node (ref "J4") (pin "4") (pinfunction "4_4") (pintype "bidirectional"))
      (node (ref "MOTORL") (pin "2") (pinfunction "2_2") (pintype "passive"))
      (node (ref "MOTORR") (pin "2") (pinfunction "2_2") (pintype "passive"))
      (node (ref "R16") (pin "2") (pinfunction "2_2") (pintype "passive"))
      (node (ref "R22") (pin "1") (pinfunction "1_1") (pintype "passive"))
      (node (ref "R24") (pin "2") (pinfunction "2_2") (pintype "passive"))
      (node (ref "U$57") (pin "VIN") (pinfunction "VIN_VIN") (pintype "bidirectional"))
      (node (ref "U1") (pin "13") (pinfunction "1_VOUT_13") (pintype "bidirectional"))
      (node (ref "U1") (pin "14") (pinfunction "2_VOUT_14") (pintype "bidirectional"))
      (node (ref "U1") (pin "15") (pinfunction "3_VOUT_15") (pintype "bidirectional"))
      (node (ref "U3") (pin "20") (pinfunction "VCC_20") (pintype "power_in"))
    )
    (net (code "3") (name "6.0V") (class "Default")
      (node (ref "C8") (pin "1") (pinfunction "P$1_1") (pintype "passive"))
      (node (ref "C9") (pin "1") (pinfunction "P$1_1") (pintype "passive"))
      (node (ref "Q2") (pin "3") (pinfunction "D_3") (pintype "passive"))
      (node (ref "R14") (pin "1") (pinfunction "1_1") (pintype "passive"))
      (node (ref "U$12") (pin "2") (pinfunction "VOUT_2") (pintype "bidirectional"))
    )
    (net (code "4") (name "ALERT") (class "Default")
      (node (ref "IC1") (pin "7") (pinfunction "ALERT_7") (pintype "output"))
    )
    (net (code "5") (name "CHG_5V") (class "Default")
      (node (ref "R13") (pin "2") (pinfunction "2_2") (pintype "passive"))
      (node (ref "U$57") (pin "13-SCK/CRX1/LED") (pinfunction "13-SCK/CRX1/LED_13-SCK/CRX1/LED") (pintype "bidirectional"))
    )
    (net (code "6") (name "ENABLE") (class "Default")
      (node (ref "R1") (pin "2") (pinfunction "2_2") (pintype "passive"))
      (node (ref "S1") (pin "2") (pinfunction "COM_2") (pintype "bidirectional"))
      (node (ref "U1") (pin "9") (pinfunction "EN_9") (pintype "bidirectional"))
    )
    (net (code "7") (name "ENCAL") (class "Default")
      (node (ref "MOTORL") (pin "3") (pinfunction "3_3") (pintype "passive"))
      (node (ref "U$57") (pin "20-A6/TX5/LRCLK1") (pinfunction "20-A6/TX5/LRCLK1_20-A6/TX5/LRCLK1") (pintype "bidirectional"))
    )
    (net (code "8") (name "ENCAR") (class "Default")
      (node (ref "MOTORR") (pin "3") (pinfunction "3_3") (pintype "passive"))
      (node (ref "U$57") (pin "2-OUT2") (pinfunction "2-OUT2_2-OUT2") (pintype "bidirectional"))
    )
    (net (code "9") (name "ENCBL") (class "Default")
      (node (ref "MOTORL") (pin "4") (pinfunction "4_4") (pintype "passive"))
      (node (ref "U$57") (pin "21-A7/RX5/BCLK1") (pinfunction "21-A7/RX5/BCLK1_21-A7/RX5/BCLK1") (pintype "bidirectional"))
    )
    (net (code "10") (name "ENCBR") (class "Default")
      (node (ref "MOTORR") (pin "4") (pinfunction "4_4") (pintype "passive"))
      (node (ref "U$57") (pin "3-LRCLK2") (pinfunction "3-LRCLK2_3-LRCLK2") (pintype "bidirectional"))
    )
    (net (code "11") (name "GND") (class "Default")
      (node (ref "B1") (pin "1") (pinfunction "-_1") (pintype "passive"))
      (node (ref "C1") (pin "1") (pinfunction "1_1") (pintype "passive"))
      (node (ref "C10") (pin "2") (pinfunction "P$2_2") (pintype "passive"))
      (node (ref "C11") (pin "2") (pinfunction "P$2_2") (pintype "passive"))
      (node (ref "C12") (pin "1") (pinfunction "P$1_1") (pintype "passive"))
      (node (ref "C13") (pin "2") (pinfunction "2_2") (pintype "passive"))
      (node (ref "C14") (pin "2") (pinfunction "2_2") (pintype "passive"))
      (node (ref "C15") (pin "2") (pinfunction "2_2") (pintype "passive"))
      (node (ref "C16") (pin "2") (pinfunction "2_2") (pintype "passive"))
      (node (ref "C17") (pin "2") (pinfunction "2_2") (pintype "passive"))
      (node (ref "C18") (pin "2") (pinfunction "2_2") (pintype "passive"))
      (node (ref "C19") (pin "2") (pinfunction "2_2") (pintype "passive"))
      (node (ref "C2") (pin "1") (pinfunction "1_1") (pintype "passive"))
      (node (ref "C20") (pin "2") (pinfunction "2_2") (pintype "passive"))
      (node (ref "C21") (pin "2") (pinfunction "2_2") (pintype "passive"))
      (node (ref "C22") (pin "2") (pinfunction "2_2") (pintype "passive"))
      (node (ref "C23") (pin "2") (pinfunction "2_2") (pintype "passive"))
      (node (ref "C24") (pin "2") (pinfunction "2_2") (pintype "passive"))
      (node (ref "C26") (pin "2") (pinfunction "2_2") (pintype "passive"))
      (node (ref "C28") (pin "2") (pinfunction "2_2") (pintype "passive"))
      (node (ref "C3") (pin "2") (pinfunction "P$2_2") (pintype "passive"))
      (node (ref "C4") (pin "1") (pinfunction "1_1") (pintype "passive"))
      (node (ref "C49") (pin "2") (pinfunction "2_2") (pintype "passive"))
      (node (ref "C7") (pin "2") (pinfunction "P$2_2") (pintype "passive"))
      (node (ref "C9") (pin "2") (pinfunction "P$2_2") (pintype "passive"))
      (node (ref "CN4") (pin "BASE@1") (pinfunction "GND_BASE@1") (pintype "power_in"))
      (node (ref "CN4") (pin "BASE@2") (pinfunction "GND_BASE@2") (pintype "power_in"))
      (node (ref "CN4") (pin "GND") (pinfunction "GND_GND") (pintype "power_in"))
      (node (ref "CN4") (pin "SPRT@1") (pinfunction "GND_SPRT@1") (pintype "power_in"))
      (node (ref "CN4") (pin "SPRT@2") (pinfunction "GND_SPRT@2") (pintype "power_in"))
      (node (ref "CN4") (pin "SPRT@3") (pinfunction "GND_SPRT@3") (pintype "power_in"))
      (node (ref "CN4") (pin "SPRT@4") (pinfunction "GND_SPRT@4") (pintype "power_in"))
      (node (ref "IC1") (pin "11") (pinfunction "GND_11") (pintype "power_in"))
      (node (ref "IC1") (pin "13") (pinfunction "GND_13") (pintype "power_in"))
      (node (ref "IC1") (pin "4") (pinfunction "A1_4") (pintype "input"))
      (node (ref "IC1") (pin "5") (pinfunction "A0_5") (pintype "input"))
      (node (ref "IC1") (pin "6") (pinfunction "GND_6") (pintype "power_in"))
      (node (ref "J4") (pin "3") (pinfunction "3_3") (pintype "bidirectional"))
      (node (ref "JD0") (pin "1") (pinfunction "1_1") (pintype "power_in"))
      (node (ref "JD1") (pin "1") (pinfunction "1_1") (pintype "power_in"))
      (node (ref "JD2") (pin "1") (pinfunction "1_1") (pintype "power_in"))
      (node (ref "JD3") (pin "1") (pinfunction "1_1") (pintype "power_in"))
      (node (ref "JD4") (pin "1") (pinfunction "1_1") (pintype "power_in"))
      (node (ref "JD5") (pin "1") (pinfunction "1_1") (pintype "power_in"))
      (node (ref "JD6") (pin "1") (pinfunction "1_1") (pintype "power_in"))
      (node (ref "LBO") (pin "C") (pinfunction "C_C") (pintype "passive"))
      (node (ref "MOTORL") (pin "5") (pinfunction "5_5") (pintype "passive"))
      (node (ref "MOTORR") (pin "5") (pinfunction "5_5") (pintype "passive"))
      (node (ref "PWR") (pin "C") (pinfunction "C_C") (pintype "passive"))
      (node (ref "Q2") (pin "1") (pinfunction "G_1") (pintype "passive"))
      (node (ref "R12") (pin "1") (pinfunction "1_1") (pintype "passive"))
      (node (ref "R120") (pin "2") (pinfunction "2_2") (pintype "passive"))
      (node (ref "R123") (pin "1") (pinfunction "1_1") (pintype "passive"))
      (node (ref "R124") (pin "1") (pinfunction "1_1") (pintype "passive"))
      (node (ref "R15") (pin "2") (pinfunction "2_2") (pintype "passive"))
      (node (ref "R25") (pin "1") (pinfunction "1_1") (pintype "passive"))
      (node (ref "R26") (pin "1") (pinfunction "1_1") (pintype "passive"))
      (node (ref "R3") (pin "5") (pinfunction "2_5") (pintype "passive"))
      (node (ref "R3") (pin "6") (pinfunction "2_6") (pintype "passive"))
      (node (ref "R50") (pin "1") (pinfunction "1_1") (pintype "passive"))
      (node (ref "S1") (pin "3") (pinfunction "NO_3") (pintype "bidirectional"))
      (node (ref "THERM6") (pin "1") (pinfunction "1_1") (pintype "passive"))
      (node (ref "U$12") (pin "1") (pinfunction "GND_1") (pintype "bidirectional"))
      (node (ref "U$12") (pin "5") (pinfunction "PG_5") (pintype "bidirectional"))
      (node (ref "U$12") (pin "P$2_GND") (pinfunction "GND_P$2_GND") (pintype "bidirectional"))
      (node (ref "U$12") (pin "P$3_GND") (pinfunction "GND_P$3_GND") (pintype "bidirectional"))
      (node (ref "U$12") (pin "THERMAL_GND") (pinfunction "GND_THERMAL_GND") (pintype "bidirectional"))
      (node (ref "U$57") (pin "GND1") (pinfunction "GND1_GND1") (pintype "bidirectional"))
      (node (ref "U$57") (pin "GND2") (pinfunction "GND2_GND2") (pintype "bidirectional"))
      (node (ref "U$57") (pin "GND3") (pinfunction "GND3_GND3") (pintype "bidirectional"))
      (node (ref "U$6") (pin "10") (pinfunction "PIN10(GND)_10") (pintype "bidirectional"))
      (node (ref "U$6") (pin "15") (pinfunction "PIN15(GND)_15") (pintype "bidirectional"))
      (node (ref "U$6") (pin "16") (pinfunction "PIN16(GND)_16") (pintype "bidirectional"))
      (node (ref "U$6") (pin "17") (pinfunction "COM3/I2C_ADDR_17") (pintype "bidirectional"))
      (node (ref "U$6") (pin "18") (pinfunction "COM2(GND)_18") (pintype "bidirectional"))
      (node (ref "U$6") (pin "2") (pinfunction "GND_2") (pintype "power_in"))
      (node (ref "U$6") (pin "25") (pinfunction "GND_25") (pintype "power_in"))
      (node (ref "U1") (pin "11") (pinfunction "GND_11") (pintype "bidirectional"))
      (node (ref "U1") (pin "16") (pinfunction "NC_16") (pintype "bidirectional"))
      (node (ref "U1") (pin "17") (pinfunction "PGND_PAD_17") (pintype "bidirectional"))
      (node (ref "U1") (pin "3") (pinfunction "1_PGND_3") (pintype "bidirectional"))
      (node (ref "U1") (pin "4") (pinfunction "2_PGND_4") (pintype "bidirectional"))
      (node (ref "U1") (pin "5") (pinfunction "3_PGND_5") (pintype "bidirectional"))
      (node (ref "U1") (pin "8") (pinfunction "SYNC_8") (pintype "bidirectional"))
      (node (ref "U1") (pin "PAD_1") (pinfunction "PGND_PAD_PAD_1") (pintype "bidirectional"))
      (node (ref "U1") (pin "PAD_2") (pinfunction "PGND_PAD_PAD_2") (pintype "bidirectional"))
      (node (ref "U1") (pin "PAD_3") (pinfunction "PGND_PAD_PAD_3") (pintype "bidirectional"))
      (node (ref "U1") (pin "PAD_4") (pinfunction "PGND_PAD_PAD_4") (pintype "bidirectional"))
      (node (ref "U1") (pin "PAD_5") (pinfunction "PGND_PAD_PAD_5") (pintype "bidirectional"))
      (node (ref "U1") (pin "PAD_6") (pinfunction "PGND_PAD_PAD_6") (pintype "bidirectional"))
      (node (ref "U16") (pin "P$10") (pinfunction "VSS1_P$10") (pintype "bidirectional"))
      (node (ref "U16") (pin "P$11") (pinfunction "VSS2_P$11") (pintype "bidirectional"))
      (node (ref "U16") (pin "P$21") (pinfunction "THERMAL_P$21") (pintype "bidirectional"))
      (node (ref "U3") (pin "10") (pinfunction "PGND2_10") (pintype "power_in"))
      (node (ref "U3") (pin "18") (pinfunction "GND_18") (pintype "power_in"))
      (node (ref "U3") (pin "3") (pinfunction "PGND1_3") (pintype "power_in"))
      (node (ref "U3") (pin "4") (pinfunction "PGND1_4") (pintype "power_in"))
      (node (ref "U3") (pin "9") (pinfunction "PGND2_9") (pintype "power_in"))
      (node (ref "U5") (pin "1") (pinfunction "A0_1") (pintype "bidirectional"))
      (node (ref "U5") (pin "12") (pinfunction "GND_12") (pintype "bidirectional"))
      (node (ref "U5") (pin "2") (pinfunction "A1_2") (pintype "bidirectional"))
      (node (ref "U5") (pin "21") (pinfunction "A2_21") (pintype "bidirectional"))
    )
    (net (code "12") (name "I2CMUX_~{RST}") (class "Default")
      (node (ref "R49") (pin "1") (pinfunction "1_1") (pintype "passive"))
      (node (ref "U$57") (pin "17-A3/TX4/SDA1") (pinfunction "17-A3/TX4/SDA1_17-A3/TX4/SDA1") (pintype "bidirectional"))
      (node (ref "U5") (pin "3") (pinfunction "~{RST}_3") (pintype "bidirectional"))
    )
    (net (code "13") (name "IMU_NRESET_3V") (class "Default")
      (node (ref "D1") (pin "A") (pinfunction "A_A") (pintype "passive"))
      (node (ref "R4") (pin "2") (pinfunction "2_2") (pintype "passive"))
      (node (ref "U$6") (pin "11") (pinfunction "NRESET_11") (pintype "bidirectional"))
    )
    (net (code "14") (name "IMU_RESET") (class "Default")
      (node (ref "D1") (pin "C") (pinfunction "C_C") (pintype "passive"))
      (node (ref "U$57") (pin "16-A2/RX4/SCL1") (pinfunction "16-A2/RX4/SCL1_16-A2/RX4/SCL1") (pintype "bidirectional"))
    )
    (net (code "15") (name "INT_3V") (class "Default")
      (node (ref "U$6") (pin "14") (pinfunction "INT_14") (pintype "output"))
    )
    (net (code "16") (name "LBO") (class "Default")
      (node (ref "T1") (pin "B") (pinfunction "B_B") (pintype "passive"))
      (node (ref "U1") (pin "10") (pinfunction "LBO_10") (pintype "bidirectional"))
    )
    (net (code "17") (name "LMIN1") (class "Default")
      (node (ref "U$57") (pin "7-RX2/OUT1A") (pinfunction "7-OUT1A/RX2_7-RX2/OUT1A") (pintype "bidirectional"))
      (node (ref "U3") (pin "17") (pinfunction "BIN1_17") (pintype "input"))
    )
    (net (code "18") (name "LMIN2") (class "Default")
      (node (ref "U$57") (pin "8-TX2/IN1") (pinfunction "8-IN1/TX2_8-TX2/IN1") (pintype "bidirectional"))
      (node (ref "U3") (pin "16") (pinfunction "BIN2_16") (pintype "input"))
    )
    (net (code "19") (name "LMOUT+") (class "Default")
      (node (ref "MOTORL") (pin "1") (pinfunction "1_1") (pintype "passive"))
      (node (ref "U3") (pin "11") (pinfunction "BOUT1_11") (pintype "output"))
      (node (ref "U3") (pin "12") (pinfunction "BOUT1_12") (pintype "output"))
    )
    (net (code "20") (name "LMOUT-") (class "Default")
      (node (ref "MOTORL") (pin "6") (pinfunction "6_6") (pintype "passive"))
      (node (ref "U3") (pin "7") (pinfunction "BOUT2_7") (pintype "output"))
      (node (ref "U3") (pin "8") (pinfunction "BOUT2_8") (pintype "output"))
    )
    (net (code "21") (name "MOT_EN") (class "Default")
      (node (ref "R2") (pin "2") (pinfunction "2_2") (pintype "passive"))
      (node (ref "U$12") (pin "6") (pinfunction "EN_6") (pintype "bidirectional"))
      (node (ref "U$57") (pin "5-IN2") (pinfunction "5-IN2_5-IN2") (pintype "bidirectional"))
    )
    (net (code "22") (name "Net-(C8-P$2)") (class "Default")
      (node (ref "C8") (pin "2") (pinfunction "P$2_2") (pintype "passive"))
      (node (ref "R14") (pin "2") (pinfunction "2_2") (pintype "passive"))
      (node (ref "R15") (pin "1") (pinfunction "1_1") (pintype "passive"))
      (node (ref "U$12") (pin "3") (pinfunction "FB_3") (pintype "bidirectional"))
    )
    (net (code "23") (name "Net-(CHRG-PadC)") (class "Default")
      (node (ref "CHRG") (pin "C") (pinfunction "C_C") (pintype "passive"))
      (node (ref "R121") (pin "2") (pinfunction "2_2") (pintype "passive"))
    )
    (net (code "24") (name "Net-(DONE-PadC)") (class "Default")
      (node (ref "DONE") (pin "C") (pinfunction "C_C") (pintype "passive"))
      (node (ref "R122") (pin "2") (pinfunction "2_2") (pintype "passive"))
    )
    (net (code "25") (name "Net-(L2-2)") (class "Default")
      (node (ref "L2") (pin "P$2") (pinfunction "2_P$2") (pintype "passive"))
      (node (ref "U$12") (pin "7") (pinfunction "SW_7") (pintype "bidirectional"))
    )
    (net (code "26") (name "Net-(L3-2)") (class "Default")
      (node (ref "L3") (pin "P$2") (pinfunction "2_P$2") (pintype "passive"))
      (node (ref "U1") (pin "1") (pinfunction "1_SW_1") (pintype "bidirectional"))
      (node (ref "U1") (pin "2") (pinfunction "2_SW_2") (pintype "bidirectional"))
    )
    (net (code "27") (name "Net-(LBO-PadA)") (class "Default")
      (node (ref "LBO") (pin "A") (pinfunction "A_A") (pintype "passive"))
      (node (ref "R21") (pin "1") (pinfunction "1_1") (pintype "passive"))
    )
    (net (code "28") (name "Net-(PWR-PadA)") (class "Default")
      (node (ref "PWR") (pin "A") (pinfunction "A_A") (pintype "passive"))
      (node (ref "R22") (pin "2") (pinfunction "2_2") (pintype "passive"))
    )
    (net (code "29") (name "Net-(R21-Pad2)") (class "Default")
      (node (ref "R21") (pin "2") (pinfunction "2_2") (pintype "passive"))
      (node (ref "T1") (pin "C") (pinfunction "C_C") (pintype "passive"))
    )
    (net (code "30") (name "Net-(R50-Pad2)") (class "Default")
      (node (ref "R50") (pin "2") (pinfunction "2_2") (pintype "passive"))
      (node (ref "TEENSY_POWER") (pin "C") (pinfunction "C_C") (pintype "passive"))
    )
    (net (code "31") (name "Net-(U$6-CAP)") (class "Default")
      (node (ref "C4") (pin "2") (pinfunction "2_2") (pintype "passive"))
      (node (ref "U$6") (pin "9") (pinfunction "CAP_9") (pintype "passive"))
    )
    (net (code "32") (name "Net-(U$6-XIN32)") (class "Default")
      (node (ref "C1") (pin "2") (pinfunction "2_2") (pintype "passive"))
      (node (ref "U$6") (pin "27") (pinfunction "XIN32_27") (pintype "input"))
      (node (ref "X2") (pin "P$2") (pinfunction "P$2_P$2") (pintype "bidirectional"))
    )
    (net (code "33") (name "Net-(U$6-XOUT32)") (class "Default")
      (node (ref "C2") (pin "2") (pinfunction "2_2") (pintype "passive"))
      (node (ref "U$6") (pin "26") (pinfunction "XOUT32_26") (pintype "output"))
      (node (ref "X2") (pin "P$1") (pinfunction "P$1_P$1") (pintype "bidirectional"))
    )
    (net (code "34") (name "Net-(U1-FB)") (class "Default")
      (node (ref "R24") (pin "1") (pinfunction "1_1") (pintype "passive"))
      (node (ref "R25") (pin "2") (pinfunction "2_2") (pintype "passive"))
      (node (ref "U1") (pin "12") (pinfunction "FB_12") (pintype "bidirectional"))
    )
    (net (code "35") (name "Net-(U1-LBI)") (class "Default")
      (node (ref "R26") (pin "2") (pinfunction "2_2") (pintype "passive"))
      (node (ref "R27") (pin "1") (pinfunction "1_1") (pintype "passive"))
      (node (ref "U1") (pin "7") (pinfunction "LBI_7") (pintype "bidirectional"))
    )
    (net (code "36") (name "Net-(U16-PROG1)") (class "Default")
      (node (ref "R123") (pin "2") (pinfunction "2_2") (pintype "passive"))
      (node (ref "U16") (pin "P$13") (pinfunction "PROG1_P$13") (pintype "bidirectional"))
    )
    (net (code "37") (name "Net-(U16-PROG3)") (class "Default")
      (node (ref "R124") (pin "2") (pinfunction "2_2") (pintype "passive"))
      (node (ref "U16") (pin "P$12") (pinfunction "PROG3_P$12") (pintype "bidirectional"))
    )
    (net (code "38") (name "Net-(U16-STAT1{slash}LBO)") (class "Default")
      (node (ref "R121") (pin "1") (pinfunction "1_1") (pintype "passive"))
      (node (ref "U16") (pin "P$8") (pinfunction "STAT1/LBO_P$8") (pintype "bidirectional"))
    )
    (net (code "39") (name "Net-(U16-STAT2)") (class "Default")
      (node (ref "R122") (pin "1") (pinfunction "1_1") (pintype "passive"))
      (node (ref "U16") (pin "P$7") (pinfunction "STAT2_P$7") (pintype "bidirectional"))
    )
    (net (code "40") (name "Net-(U16-THERM)") (class "Default")
      (node (ref "THERM6") (pin "2") (pinfunction "2_2") (pintype "passive"))
      (node (ref "U16") (pin "P$5") (pinfunction "THERM_P$5") (pintype "bidirectional"))
    )
    (net (code "41") (name "Net-(U16-VPCC)") (class "Default")
      (node (ref "R119") (pin "1") (pinfunction "1_1") (pintype "passive"))
      (node (ref "R120") (pin "1") (pinfunction "1_1") (pintype "passive"))
      (node (ref "U16") (pin "P$2") (pinfunction "VPCC_P$2") (pintype "bidirectional"))
    )
    (net (code "42") (name "PS0_3V") (class "Default")
      (node (ref "R3") (pin "3") (pinfunction "1_3") (pintype "passive"))
      (node (ref "U$6") (pin "6") (pinfunction "PS0_6") (pintype "input"))
    )
    (net (code "43") (name "PS1_3V") (class "Default")
      (node (ref "R3") (pin "4") (pinfunction "1_4") (pintype "passive"))
      (node (ref "U$6") (pin "5") (pinfunction "PS1_5") (pintype "input"))
    )
    (net (code "44") (name "PWML") (class "Default")
      (node (ref "U$57") (pin "23-A9/CRX1/CCLK1") (pinfunction "23-A9/CRX1/MCLK1_23-A9/CRX1/CCLK1") (pintype "bidirectional"))
      (node (ref "U3") (pin "15") (pinfunction "PWMB_15") (pintype "input"))
    )
    (net (code "45") (name "PWMR") (class "Default")
      (node (ref "U$57") (pin "4-BCLK2") (pinfunction "4-BCLK1_4-BCLK2") (pintype "bidirectional"))
      (node (ref "U3") (pin "23") (pinfunction "PWMA_23") (pintype "input"))
    )
    (net (code "46") (name "RMIN1") (class "Default")
      (node (ref "U$57") (pin "0-RX1") (pinfunction "0-RX1/CRX2_0-RX1") (pintype "bidirectional"))
      (node (ref "U3") (pin "21") (pinfunction "AIN1_21") (pintype "input"))
    )
    (net (code "47") (name "RMIN2") (class "Default")
      (node (ref "U$57") (pin "1-TX1") (pinfunction "1-TX1/CTX2_1-TX1") (pintype "bidirectional"))
      (node (ref "U3") (pin "22") (pinfunction "AIN2_22") (pintype "input"))
    )
    (net (code "48") (name "RMOUT+") (class "Default")
      (node (ref "MOTORR") (pin "1") (pinfunction "1_1") (pintype "passive"))
      (node (ref "U3") (pin "1") (pinfunction "AOUT1_1") (pintype "output"))
      (node (ref "U3") (pin "2") (pinfunction "AOUT1_2") (pintype "output"))
    )
    (net (code "49") (name "RMOUT-") (class "Default")
      (node (ref "MOTORR") (pin "6") (pinfunction "6_6") (pintype "passive"))
      (node (ref "U3") (pin "5") (pinfunction "AOUT2_5") (pintype "output"))
      (node (ref "U3") (pin "6") (pinfunction "AOUT2_6") (pintype "output"))
    )
    (net (code "50") (name "RPI_RX") (class "Default")
      (node (ref "J4") (pin "1") (pinfunction "1_1") (pintype "bidirectional"))
      (node (ref "U$57") (pin "14-A0/TX3/S-PFI_OUT") (pinfunction "14-A0/TX3/S-PDIF_IN_14-A0/TX3/S-PFI_OUT") (pintype "bidirectional"))
    )
    (net (code "51") (name "RPI_TX") (class "Default")
      (node (ref "J4") (pin "2") (pinfunction "2_2") (pintype "bidirectional"))
      (node (ref "U$57") (pin "15-A1/RX3/S-PDIF_IN") (pinfunction "15-A1/RX3/SPDIF_IN_15-A1/RX3/S-PDIF_IN") (pintype "bidirectional"))
    )
    (net (code "52") (name "SCL0") (class "Default")
      (node (ref "JD0") (pin "4") (pinfunction "4_4") (pintype "passive"))
      (node (ref "R29") (pin "2") (pinfunction "2_2") (pintype "passive"))
      (node (ref "U5") (pin "5") (pinfunction "SC0_5") (pintype "bidirectional"))
    )
    (net (code "53") (name "SCL1") (class "Default")
      (node (ref "JD1") (pin "4") (pinfunction "4_4") (pintype "passive"))
      (node (ref "R31") (pin "2") (pinfunction "2_2") (pintype "passive"))
      (node (ref "U5") (pin "7") (pinfunction "SC1_7") (pintype "bidirectional"))
    )
    (net (code "54") (name "SCL2") (class "Default")
      (node (ref "JD2") (pin "4") (pinfunction "4_4") (pintype "passive"))
      (node (ref "R33") (pin "2") (pinfunction "2_2") (pintype "passive"))
      (node (ref "U5") (pin "9") (pinfunction "SC2_9") (pintype "bidirectional"))
    )
    (net (code "55") (name "SCL3") (class "Default")
      (node (ref "JD3") (pin "4") (pinfunction "4_4") (pintype "passive"))
      (node (ref "R35") (pin "2") (pinfunction "2_2") (pintype "passive"))
      (node (ref "U5") (pin "11") (pinfunction "SC3_11") (pintype "bidirectional"))
    )
    (net (code "56") (name "SCL4") (class "Default")
      (node (ref "JD4") (pin "4") (pinfunction "4_4") (pintype "passive"))
      (node (ref "R37") (pin "2") (pinfunction "2_2") (pintype "passive"))
      (node (ref "U5") (pin "14") (pinfunction "SC4_14") (pintype "bidirectional"))
    )
    (net (code "57") (name "SCL5") (class "Default")
      (node (ref "JD5") (pin "4") (pinfunction "4_4") (pintype "passive"))
      (node (ref "R39") (pin "2") (pinfunction "2_2") (pintype "passive"))
      (node (ref "U5") (pin "16") (pinfunction "SC5_16") (pintype "bidirectional"))
    )
    (net (code "58") (name "SCL6") (class "Default")
      (node (ref "JD6") (pin "4") (pinfunction "4_4") (pintype "passive"))
      (node (ref "R41") (pin "2") (pinfunction "2_2") (pintype "passive"))
      (node (ref "U5") (pin "18") (pinfunction "SC6_18") (pintype "bidirectional"))
    )
    (net (code "59") (name "SCL_MAIN") (class "Default")
      (node (ref "IC1") (pin "9") (pinfunction "SCL_9") (pintype "bidirectional"))
      (node (ref "R9") (pin "8") (pinfunction "2_8") (pintype "passive"))
      (node (ref "U$57") (pin "19-A5/SCL0") (pinfunction "19-A5/SCL0_19-A5/SCL0") (pintype "bidirectional"))
      (node (ref "U$6") (pin "19") (pinfunction "COM1/SCL/RX_19") (pintype "bidirectional"))
      (node (ref "U5") (pin "22") (pinfunction "SCL_22") (pintype "bidirectional"))
    )
    (net (code "60") (name "SDA0") (class "Default")
      (node (ref "JD0") (pin "3") (pinfunction "3_3") (pintype "passive"))
      (node (ref "R28") (pin "2") (pinfunction "2_2") (pintype "passive"))
      (node (ref "U5") (pin "4") (pinfunction "SD0_4") (pintype "bidirectional"))
    )
    (net (code "61") (name "SDA1") (class "Default")
      (node (ref "JD1") (pin "3") (pinfunction "3_3") (pintype "passive"))
      (node (ref "R30") (pin "2") (pinfunction "2_2") (pintype "passive"))
      (node (ref "U5") (pin "6") (pinfunction "SD1_6") (pintype "bidirectional"))
    )
    (net (code "62") (name "SDA2") (class "Default")
      (node (ref "JD2") (pin "3") (pinfunction "3_3") (pintype "passive"))
      (node (ref "R32") (pin "2") (pinfunction "2_2") (pintype "passive"))
      (node (ref "U5") (pin "8") (pinfunction "SD2_8") (pintype "bidirectional"))
    )
    (net (code "63") (name "SDA3") (class "Default")
      (node (ref "JD3") (pin "3") (pinfunction "3_3") (pintype "passive"))
      (node (ref "R34") (pin "2") (pinfunction "2_2") (pintype "passive"))
      (node (ref "U5") (pin "10") (pinfunction "SD3_10") (pintype "bidirectional"))
    )
    (net (code "64") (name "SDA4") (class "Default")
      (node (ref "JD4") (pin "3") (pinfunction "3_3") (pintype "passive"))
      (node (ref "R36") (pin "2") (pinfunction "2_2") (pintype "passive"))
      (node (ref "U5") (pin "13") (pinfunction "SD4_13") (pintype "bidirectional"))
    )
    (net (code "65") (name "SDA5") (class "Default")
      (node (ref "JD5") (pin "3") (pinfunction "3_3") (pintype "passive"))
      (node (ref "R38") (pin "2") (pinfunction "2_2") (pintype "passive"))
      (node (ref "U5") (pin "15") (pinfunction "SD5_15") (pintype "bidirectional"))
    )
    (net (code "66") (name "SDA6") (class "Default")
      (node (ref "JD6") (pin "3") (pinfunction "3_3") (pintype "passive"))
      (node (ref "R40") (pin "2") (pinfunction "2_2") (pintype "passive"))
      (node (ref "U5") (pin "17") (pinfunction "SD6_17") (pintype "bidirectional"))
    )
    (net (code "67") (name "SDA_MAIN") (class "Default")
      (node (ref "IC1") (pin "8") (pinfunction "SDA_8") (pintype "bidirectional"))
      (node (ref "R9") (pin "5") (pinfunction "2_5") (pintype "passive"))
      (node (ref "U$57") (pin "18-A4/SDA0") (pinfunction "18-A4/SDA0_18-A4/SDA0") (pintype "bidirectional"))
      (node (ref "U$6") (pin "20") (pinfunction "COM0/SDA/TX_20") (pintype "bidirectional"))
      (node (ref "U5") (pin "23") (pinfunction "SDA_23") (pintype "bidirectional"))
    )
    (net (code "68") (name "STBY") (class "Default")
      (node (ref "R16") (pin "1") (pinfunction "1_1") (pintype "passive"))
      (node (ref "U$57") (pin "6-OUT1D") (pinfunction "6-OUT1D_6-OUT1D") (pintype "bidirectional"))
      (node (ref "U3") (pin "19") (pinfunction "STBY_19") (pintype "input"))
    )
    (net (code "69") (name "VBAT") (class "Default")
      (node (ref "C13") (pin "1") (pinfunction "1_1") (pintype "passive"))
      (node (ref "C15") (pin "1") (pinfunction "1_1") (pintype "passive"))
      (node (ref "C3") (pin "1") (pinfunction "P$1_1") (pintype "passive"))
      (node (ref "C7") (pin "1") (pinfunction "P$1_1") (pintype "passive"))
      (node (ref "L2") (pin "P$1") (pinfunction "1_P$1") (pintype "passive"))
      (node (ref "L3") (pin "P$1") (pinfunction "1_P$1") (pintype "passive"))
      (node (ref "R1") (pin "1") (pinfunction "1_1") (pintype "passive"))
      (node (ref "R2") (pin "1") (pinfunction "1_1") (pintype "passive"))
      (node (ref "R27") (pin "2") (pinfunction "2_2") (pintype "passive"))
      (node (ref "T1") (pin "E") (pinfunction "E_E") (pintype "passive"))
      (node (ref "U$12") (pin "4") (pinfunction "ILIM_4") (pintype "bidirectional"))
      (node (ref "U$12") (pin "8") (pinfunction "VIN_8") (pintype "bidirectional"))
      (node (ref "U1") (pin "6") (pinfunction "VBAT_6") (pintype "bidirectional"))
      (node (ref "U16") (pin "P$1") (pinfunction "VOUT1_P$1") (pintype "bidirectional"))
      (node (ref "U16") (pin "P$20") (pinfunction "VOUT2_P$20") (pintype "bidirectional"))
    )
    (net (code "70") (name "VBAT_IN") (class "Default")
      (node (ref "B1") (pin "2") (pinfunction "+_2") (pintype "passive"))
      (node (ref "C49") (pin "1") (pinfunction "1_1") (pintype "passive"))
      (node (ref "IC1") (pin "1") (pinfunction "IN+_1") (pintype "bidirectional"))
      (node (ref "IC1") (pin "12") (pinfunction "VBUS_12") (pintype "power_in"))
      (node (ref "IC1") (pin "2") (pinfunction "IN+_2") (pintype "bidirectional"))
      (node (ref "IC1") (pin "3") (pinfunction "IN+_3") (pintype "bidirectional"))
      (node (ref "JP1") (pin "1") (pinfunction "1_1") (pintype "passive"))
      (node (ref "R11") (pin "2") (pinfunction "2_2") (pintype "passive"))
    )
    (net (code "71") (name "VBAT_MEASURE") (class "Default")
      (node (ref "R11") (pin "1") (pinfunction "1_1") (pintype "passive"))
      (node (ref "R12") (pin "2") (pinfunction "2_2") (pintype "passive"))
      (node (ref "U$57") (pin "22-A8/CTX1") (pinfunction "22-A8/CTX1_22-A8/CTX1") (pintype "bidirectional"))
    )
    (net (code "72") (name "VBUS") (class "Default")
      (node (ref "C17") (pin "1") (pinfunction "1_1") (pintype "passive"))
      (node (ref "CHRG") (pin "A") (pinfunction "A_A") (pintype "passive"))
      (node (ref "CN4") (pin "VBUS") (pinfunction "VBUS_VBUS") (pintype "power_in"))
      (node (ref "DONE") (pin "A") (pinfunction "A_A") (pintype "passive"))
      (node (ref "R119") (pin "2") (pinfunction "2_2") (pintype "passive"))
      (node (ref "R13") (pin "1") (pinfunction "1_1") (pintype "passive"))
      (node (ref "U16") (pin "P$17") (pinfunction "CE_P$17") (pintype "bidirectional"))
      (node (ref "U16") (pin "P$18") (pinfunction "VIN1_P$18") (pintype "bidirectional"))
      (node (ref "U16") (pin "P$19") (pinfunction "VIN2_P$19") (pintype "bidirectional"))
      (node (ref "U16") (pin "P$3") (pinfunction "SEL_P$3") (pintype "bidirectional"))
      (node (ref "U16") (pin "P$4") (pinfunction "PROG2_P$4") (pintype "bidirectional"))
      (node (ref "U16") (pin "P$9") (pinfunction "/TE_P$9") (pintype "bidirectional"))
    )
    (net (code "73") (name "VMOTOR") (class "Default")
      (node (ref "C11") (pin "1") (pinfunction "P$1_1") (pintype "passive"))
      (node (ref "Q2") (pin "2") (pinfunction "S_2") (pintype "passive"))
      (node (ref "U3") (pin "13") (pinfunction "VM_13") (pintype "power_in"))
      (node (ref "U3") (pin "14") (pinfunction "VM_14") (pintype "power_in"))
      (node (ref "U3") (pin "24") (pinfunction "VM_24") (pintype "power_in"))
    )
    (net (code "74") (name "V_PWR") (class "Default")
      (node (ref "IC1") (pin "14") (pinfunction "IN-_14") (pintype "bidirectional"))
      (node (ref "IC1") (pin "15") (pinfunction "IN-_15") (pintype "bidirectional"))
      (node (ref "IC1") (pin "16") (pinfunction "IN-_16") (pintype "bidirectional"))
      (node (ref "JP1") (pin "2") (pinfunction "2_2") (pintype "passive"))
      (node (ref "U16") (pin "P$14") (pinfunction "VBAT1_P$14") (pintype "bidirectional"))
      (node (ref "U16") (pin "P$15") (pinfunction "VBAT2_P$15") (pintype "bidirectional"))
      (node (ref "U16") (pin "P$16") (pinfunction "VBATSENS_P$16") (pintype "bidirectional"))
    )
    (net (code "75") (name "unconnected-(CN4-PadD+)") (class "Default")
      (node (ref "CN4") (pin "D+") (pinfunction "D+_D+") (pintype "bidirectional"))
    )
    (net (code "76") (name "unconnected-(CN4-PadD-)") (class "Default")
      (node (ref "CN4") (pin "D-") (pinfunction "D-_D-") (pintype "bidirectional"))
    )
    (net (code "77") (name "unconnected-(CN4-PadID)") (class "Default")
      (node (ref "CN4") (pin "ID") (pinfunction "ID_ID") (pintype "bidirectional"))
    )
    (net (code "78") (name "unconnected-(S1-NC-Pad1)") (class "Default")
      (node (ref "S1") (pin "1") (pinfunction "NC_1") (pintype "no_connect"))
    )
    (net (code "79") (name "unconnected-(U$6-PIN7(SWDIO)-Pad7)") (class "Default")
      (node (ref "U$6") (pin "7") (pinfunction "PIN7(SWDIO)_7") (pintype "bidirectional"))
    )
    (net (code "80") (name "unconnected-(U$57-10-CS-Pad10-CS{slash}MQSR)") (class "Default")
      (node (ref "U$57") (pin "10-CS/MQSR") (pinfunction "10-CS_10-CS/MQSR") (pintype "bidirectional"))
    )
    (net (code "81") (name "unconnected-(U$57-12-MISO{slash}MQSL-Pad12-MIO{slash}MQSL)") (class "Default")
      (node (ref "U$57") (pin "12-MIO/MQSL") (pinfunction "12-MISO/MQSL_12-MIO/MQSL") (pintype "bidirectional"))
    )
    (net (code "82") (name "unconnected-(U$57-25-A11{slash}RX6{slash}SDA2-Pad25-A11{slash}SDA2)") (class "Default")
      (node (ref "U$57") (pin "25-A11/SDA2") (pinfunction "25-A11/RX6/SDA2_25-A11/SDA2") (pintype "bidirectional"))
    )
    (net (code "83") (name "unconnected-(U$57-32-OUT1B-Pad32-OUTB1)") (class "Default")
      (node (ref "U$57") (pin "32-OUTB1") (pinfunction "32-OUT1B_32-OUTB1") (pintype "bidirectional"))
    )
    (net (code "84") (name "unconnected-(U$57-Pad3V3-2)") (class "Default")
      (node (ref "U$57") (pin "3V3-2") (pinfunction "3V3-2_3V3-2") (pintype "bidirectional"))
    )
    (net (code "85") (name "unconnected-(U$57-Pad9-OUT1C)") (class "Default")
      (node (ref "U$57") (pin "9-OUT1C") (pinfunction "9-OUT1C_9-OUT1C") (pintype "bidirectional"))
    )
    (net (code "86") (name "unconnected-(U$57-Pad11-MOSI{slash}CTX1)") (class "Default")
      (node (ref "U$57") (pin "11-MOSI/CTX1") (pinfunction "11-MOSI/CTX1_11-MOSI/CTX1") (pintype "bidirectional"))
    )
    (net (code "87") (name "unconnected-(U$57-Pad24-A10{slash}TX6{slash}SCL2)") (class "Default")
      (node (ref "U$57") (pin "24-A10/TX6/SCL2") (pinfunction "24-A10/TX6/SCL2_24-A10/TX6/SCL2") (pintype "bidirectional"))
    )
    (net (code "88") (name "unconnected-(U$57-Pad26-A12{slash}MOSI1)") (class "Default")
      (node (ref "U$57") (pin "26-A12/MOSI1") (pinfunction "26-A12/MOSI1_26-A12/MOSI1") (pintype "bidirectional"))
    )
    (net (code "89") (name "unconnected-(U$57-Pad27-A13{slash}SCK1)") (class "Default")
      (node (ref "U$57") (pin "27-A13/SCK1") (pinfunction "27-A13/SCK1_27-A13/SCK1") (pintype "bidirectional"))
    )
    (net (code "90") (name "unconnected-(U$57-Pad28-RX7)") (class "Default")
      (node (ref "U$57") (pin "28-RX7") (pinfunction "28-RX7_28-RX7") (pintype "bidirectional"))
    )
    (net (code "91") (name "unconnected-(U$57-Pad29-TX7)") (class "Default")
      (node (ref "U$57") (pin "29-TX7") (pinfunction "29-TX7_29-TX7") (pintype "bidirectional"))
    )
    (net (code "92") (name "unconnected-(U$57-Pad30-CRX3)") (class "Default")
      (node (ref "U$57") (pin "30-CRX3") (pinfunction "30-CRX3_30-CRX3") (pintype "bidirectional"))
    )
    (net (code "93") (name "unconnected-(U$57-Pad31-CTX3)") (class "Default")
      (node (ref "U$57") (pin "31-CTX3") (pinfunction "31-CTX3_31-CTX3") (pintype "bidirectional"))
    )
    (net (code "94") (name "unconnected-(U$57-Pad33-MCLK2)") (class "Default")
      (node (ref "U$57") (pin "33-MCLK2") (pinfunction "33-MCLK2_33-MCLK2") (pintype "bidirectional"))
    )
    (net (code "95") (name "unconnected-(U$57-PadON{slash}OFF)") (class "Default")
      (node (ref "U$57") (pin "ON/OFF") (pinfunction "ON/OFF_ON/OFF") (pintype "bidirectional"))
    )
    (net (code "96") (name "unconnected-(U$57-PadPROGRAM)") (class "Default")
      (node (ref "U$57") (pin "PROGRAM") (pinfunction "PROGRAM_PROGRAM") (pintype "bidirectional"))
    )
    (net (code "97") (name "unconnected-(U$57-PadVBAT)") (class "Default")
      (node (ref "U$57") (pin "VBAT") (pinfunction "VBAT_VBAT") (pintype "bidirectional"))
    )
    (net (code "98") (name "unconnected-(U$57-PadVUSB)") (class "Default")
      (node (ref "U$57") (pin "VUSB") (pinfunction "VUSB_VUSB") (pintype "bidirectional"))
    )
    (net (code "99") (name "unconnected-(U5-SC7-Pad20)") (class "Default")
      (node (ref "U5") (pin "20") (pinfunction "SC7_20") (pintype "bidirectional"))
    )
    (net (code "100") (name "unconnected-(U5-SD7-Pad19)") (class "Default")
      (node (ref "U5") (pin "19") (pinfunction "SD7_19") (pintype "bidirectional"))
    )
    (net (code "101") (name "unconnected-(U16-{slash}PG-PadP$6)") (class "Default")
      (node (ref "U16") (pin "P$6") (pinfunction "/PG_P$6") (pintype "bidirectional"))
    )
  )
)
